# ArbotixProv11.net
KiCad netlist of a schematic drawn in EAGLE
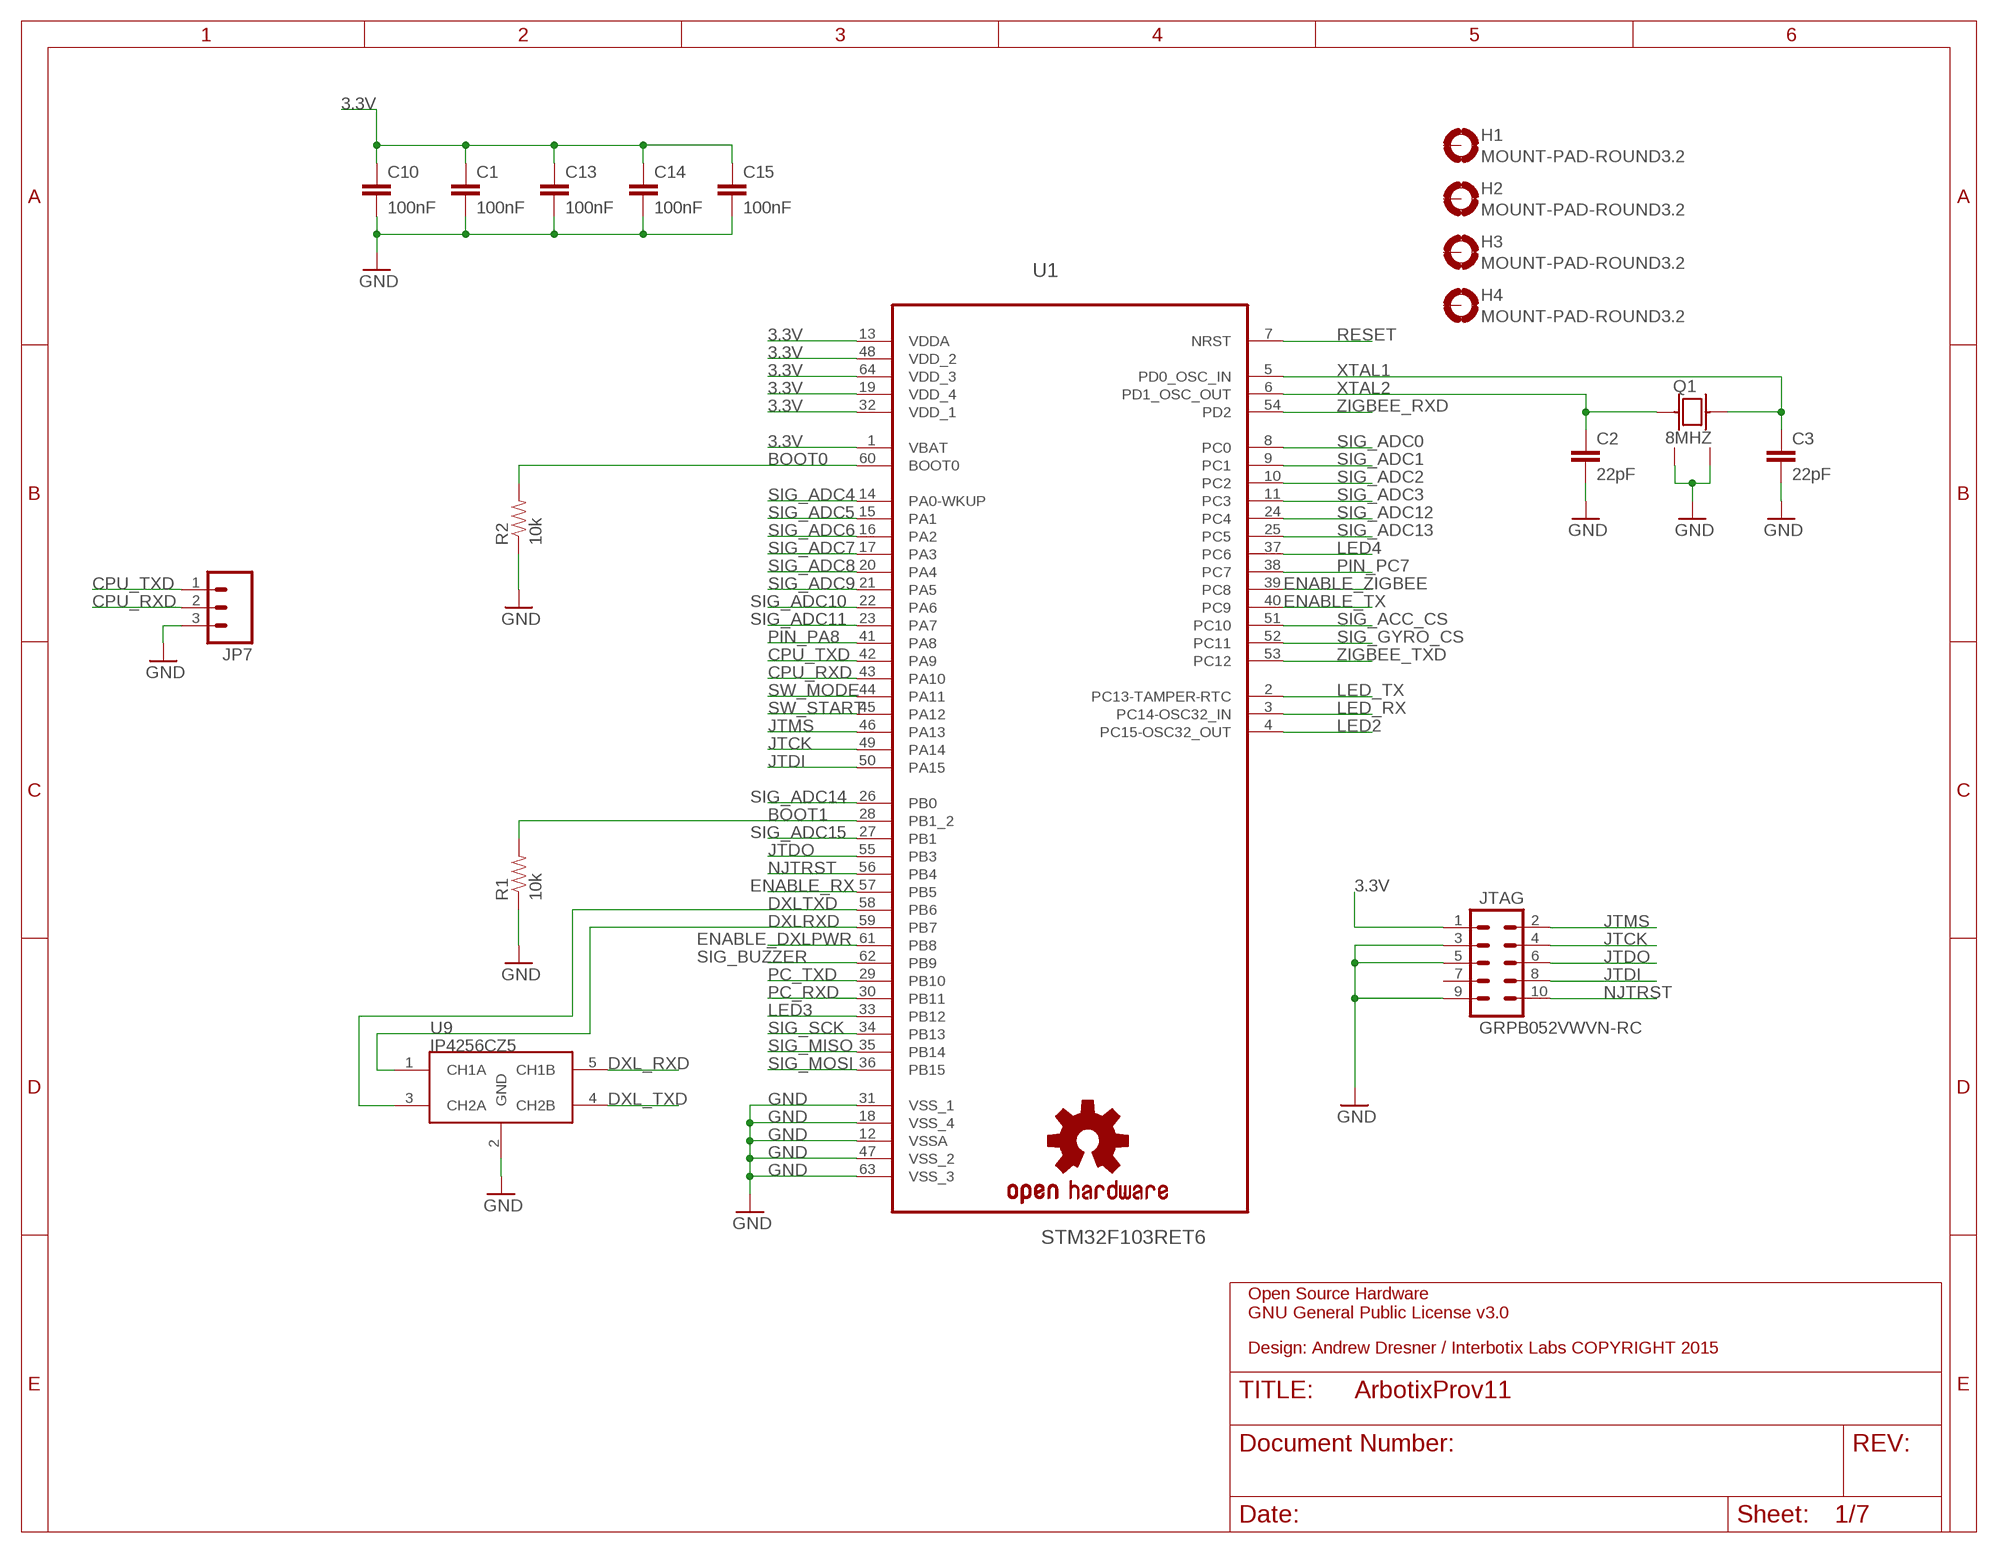
[diagram p0: schematic, sheet 1]
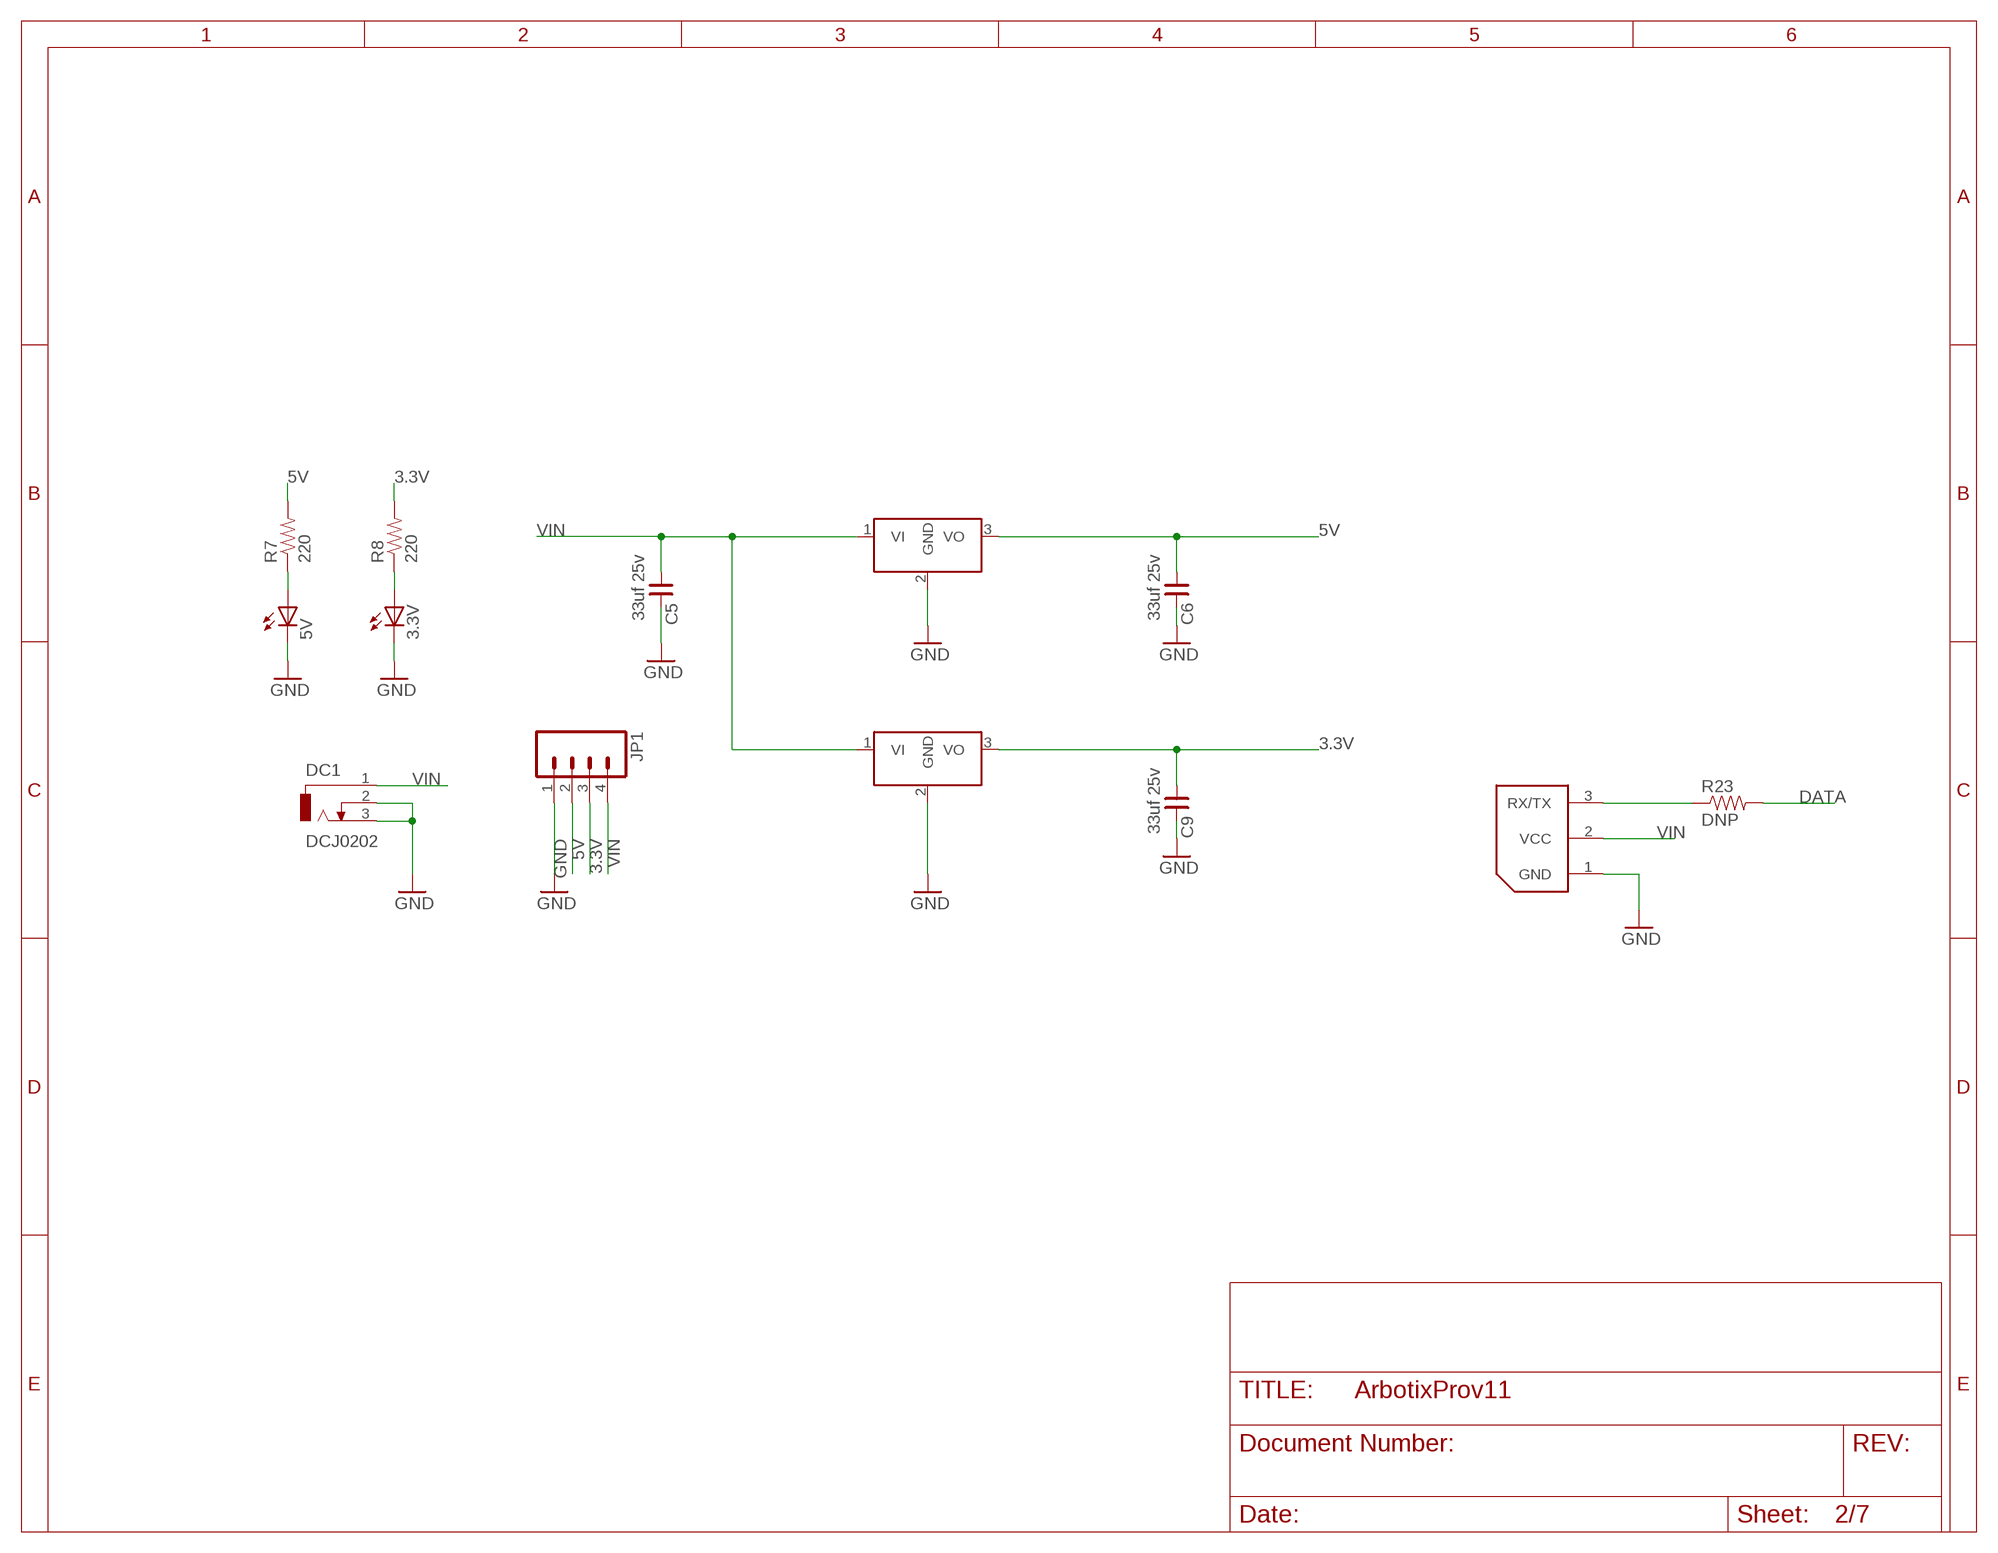
[diagram p1: schematic, sheet 2]
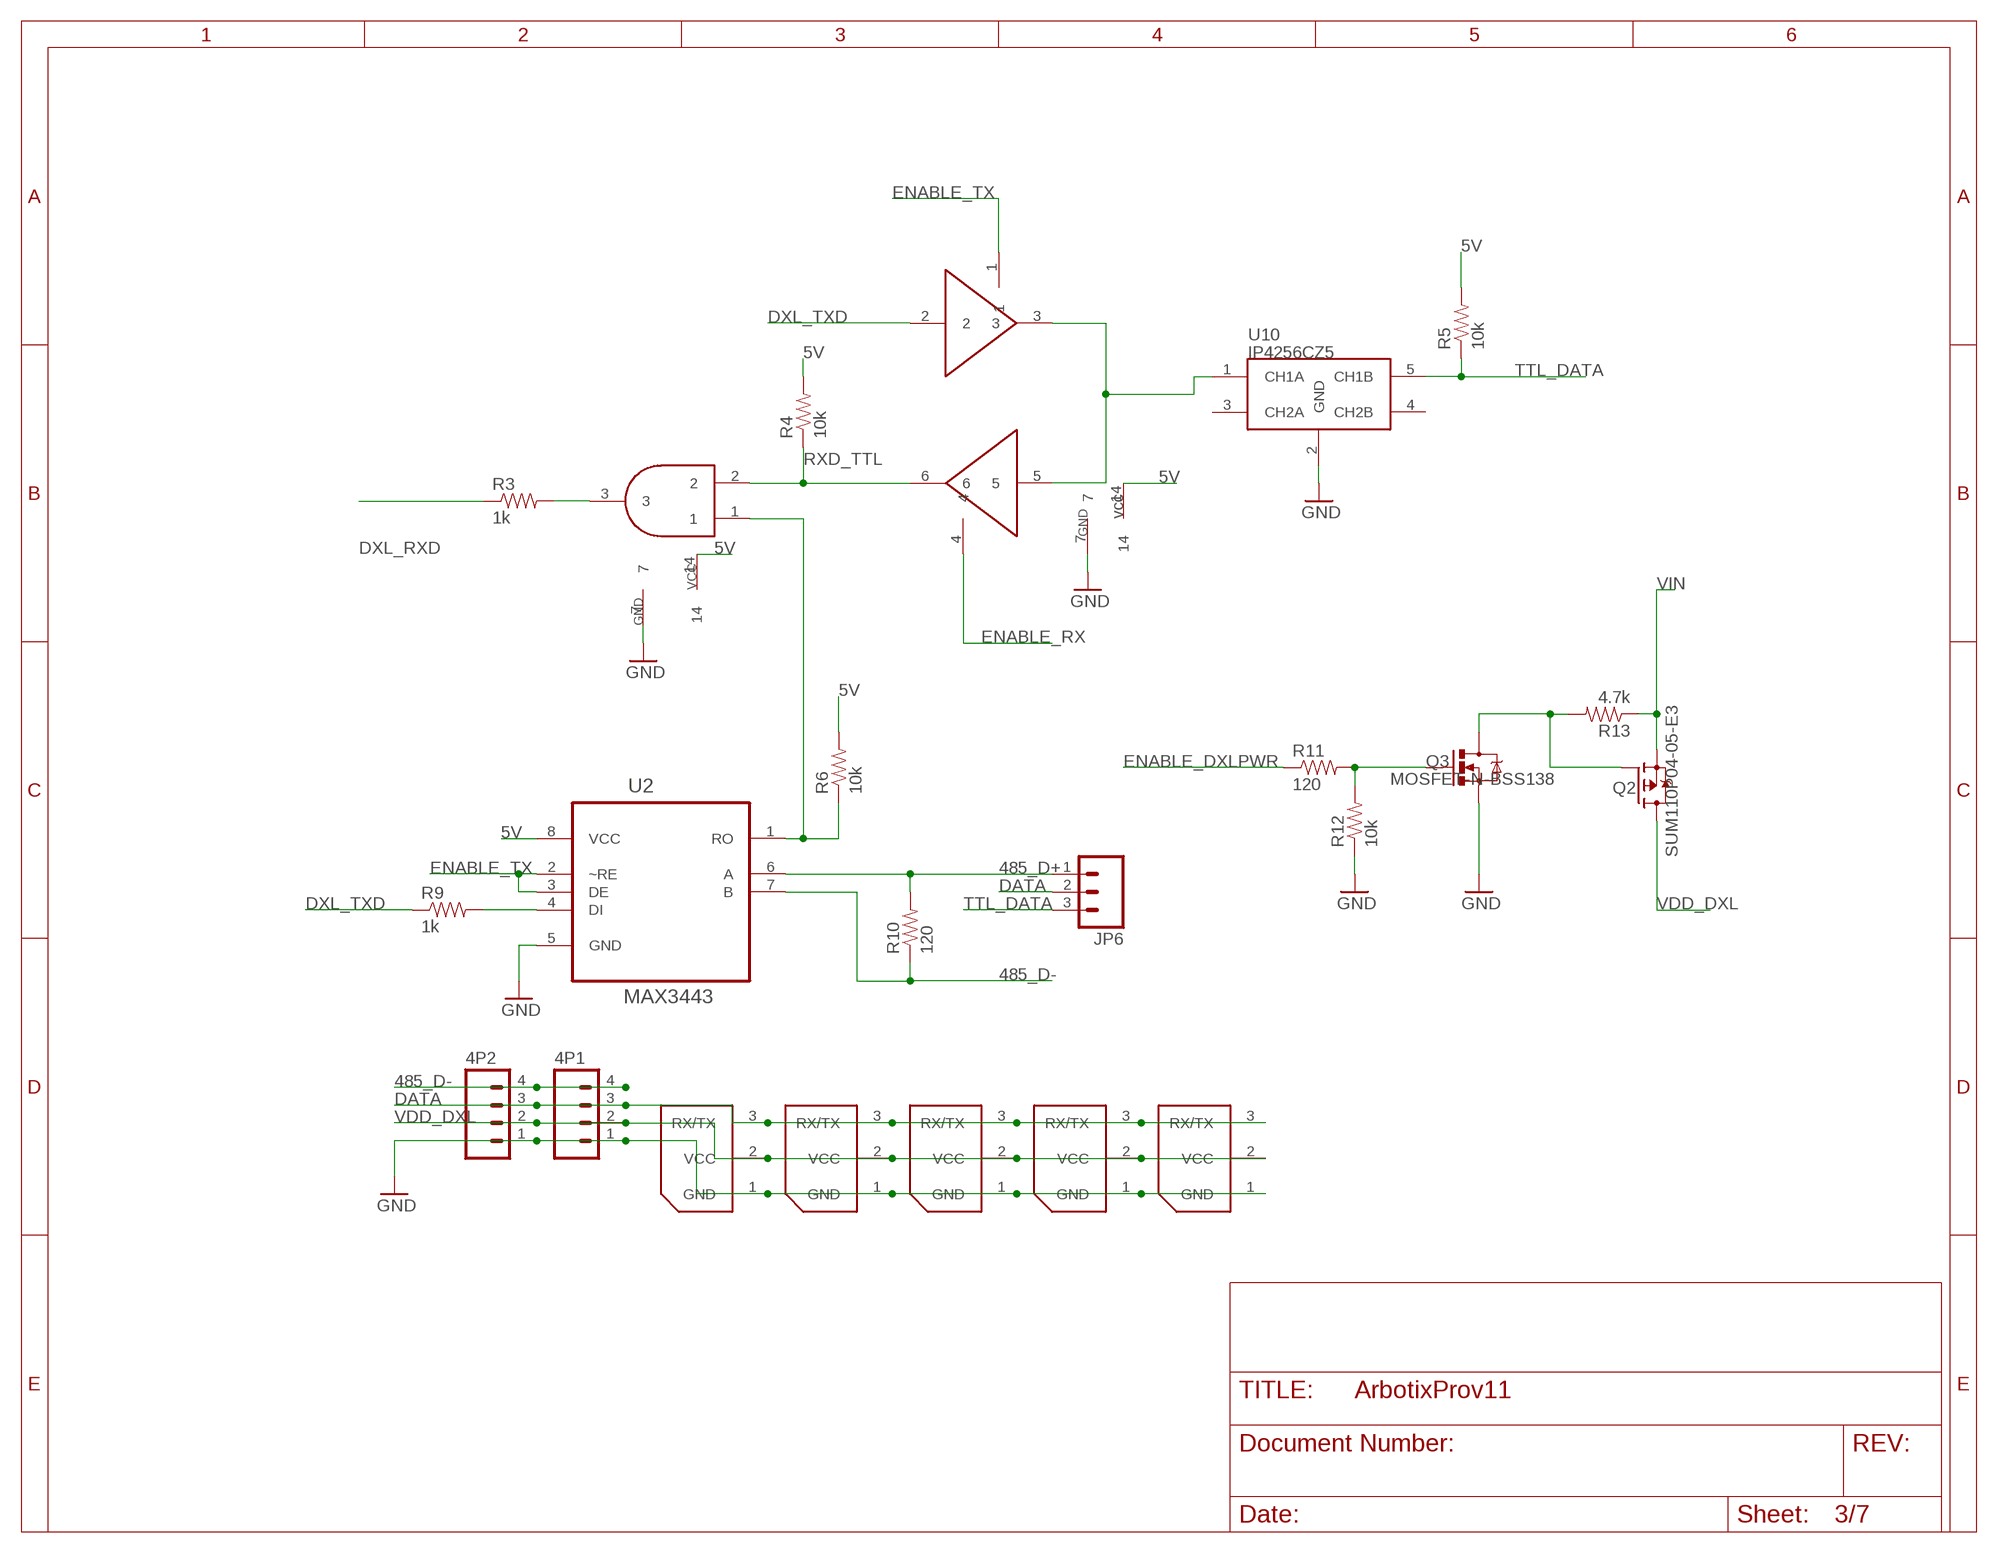
[diagram p2: schematic, sheet 3]
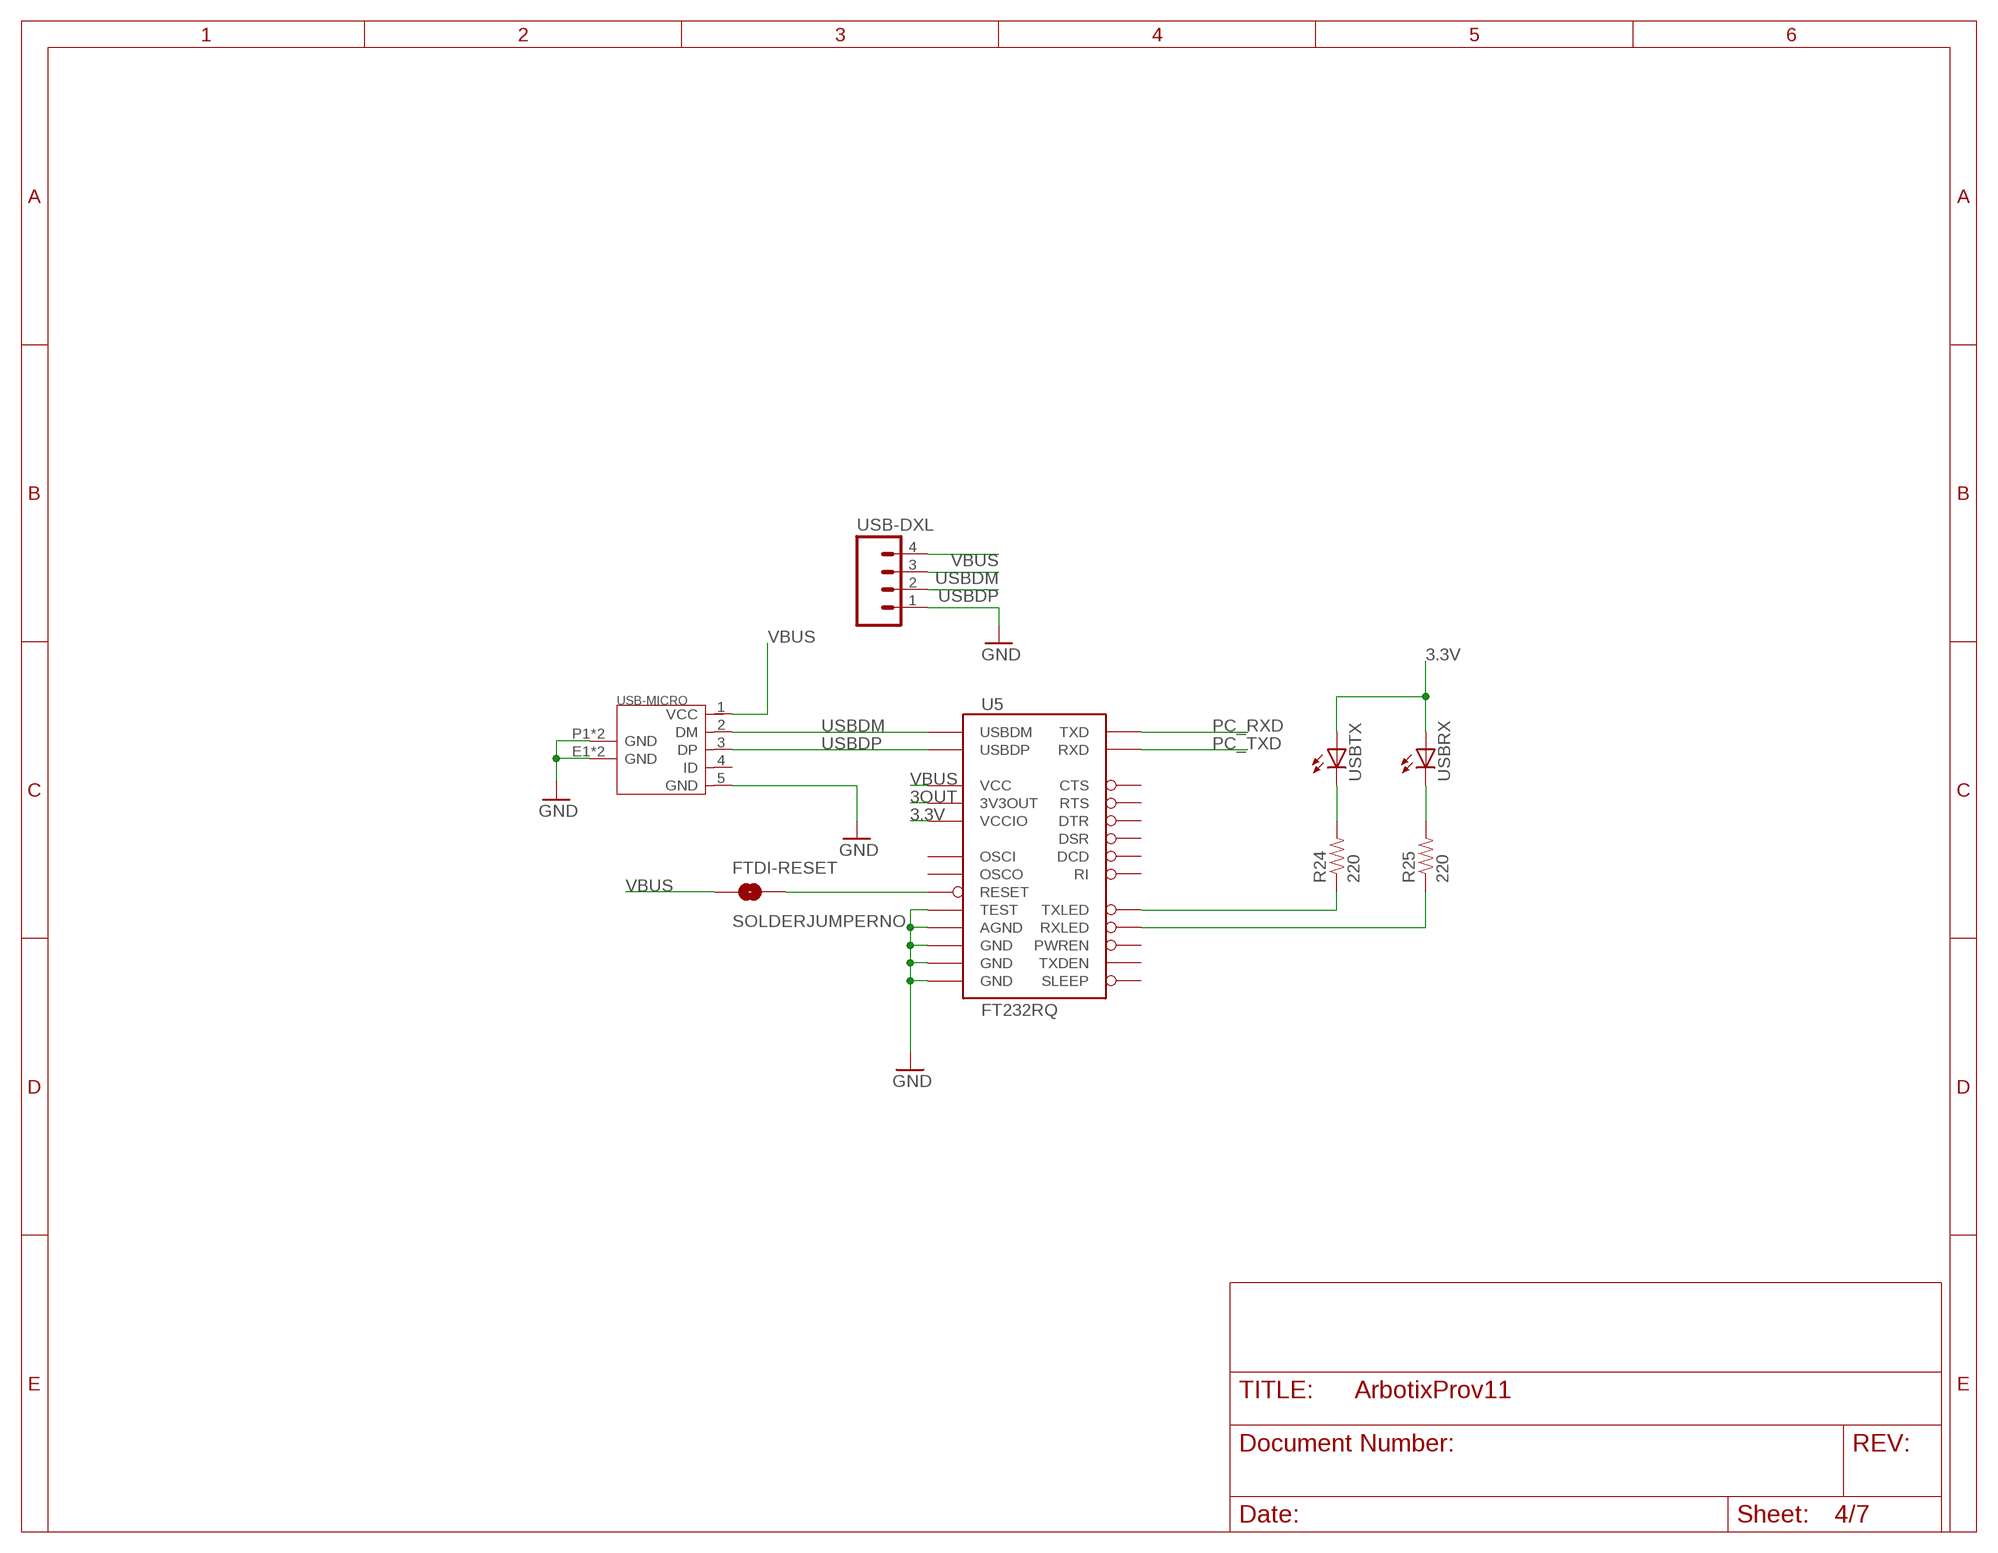
[diagram p3: schematic, sheet 4]
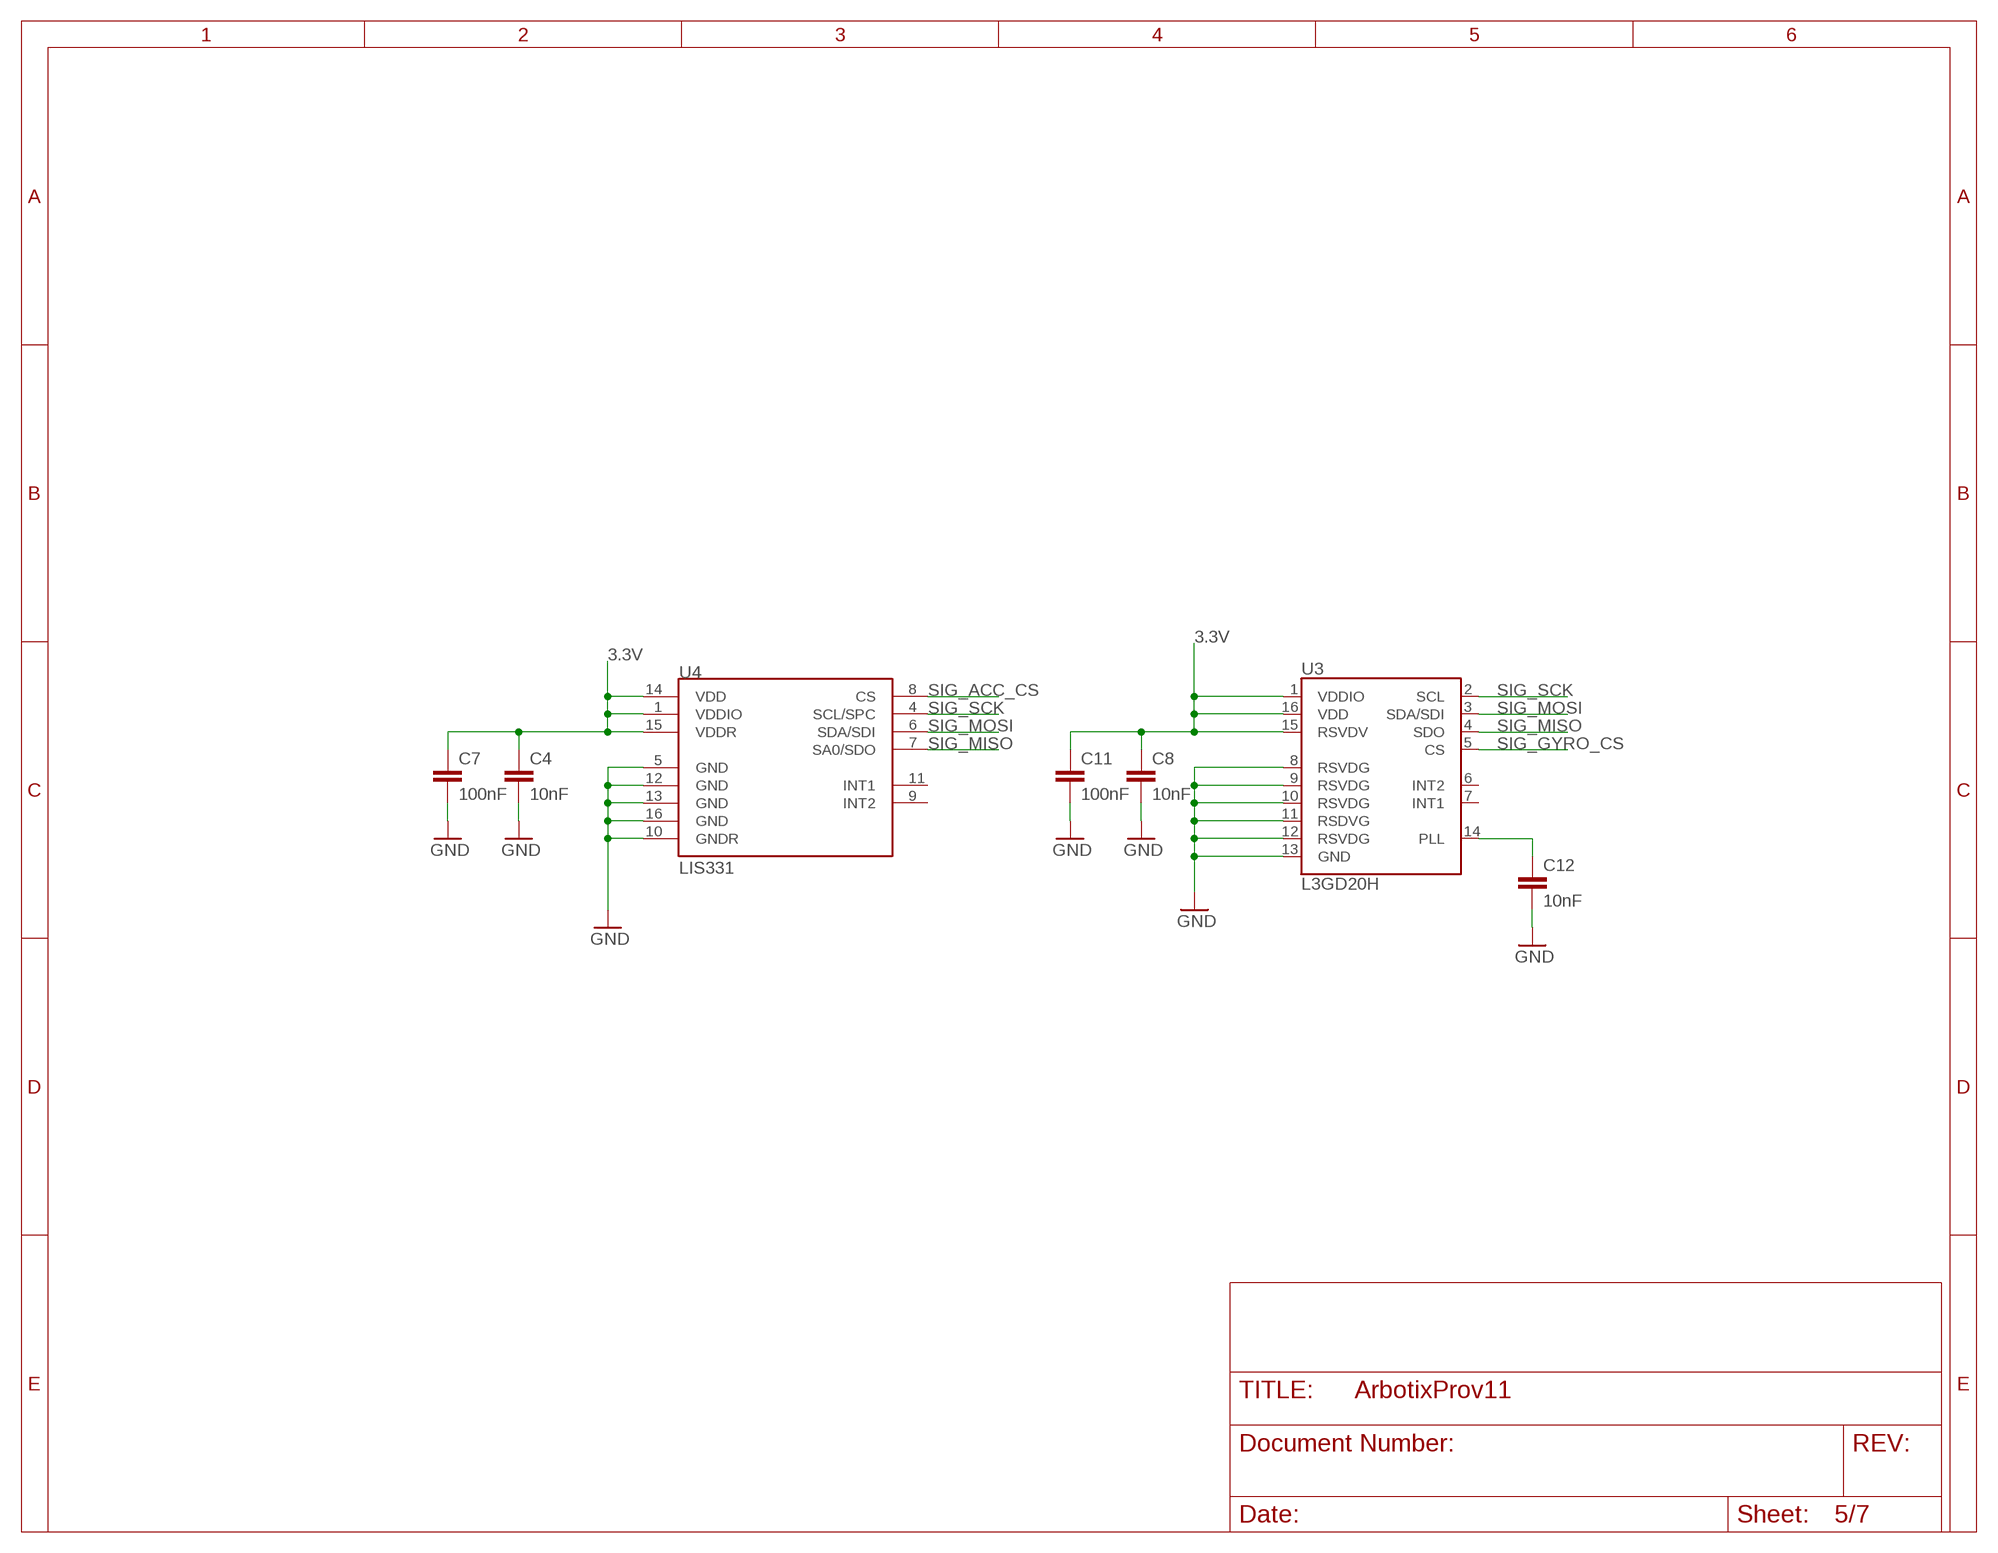
[diagram p4: schematic, sheet 5]
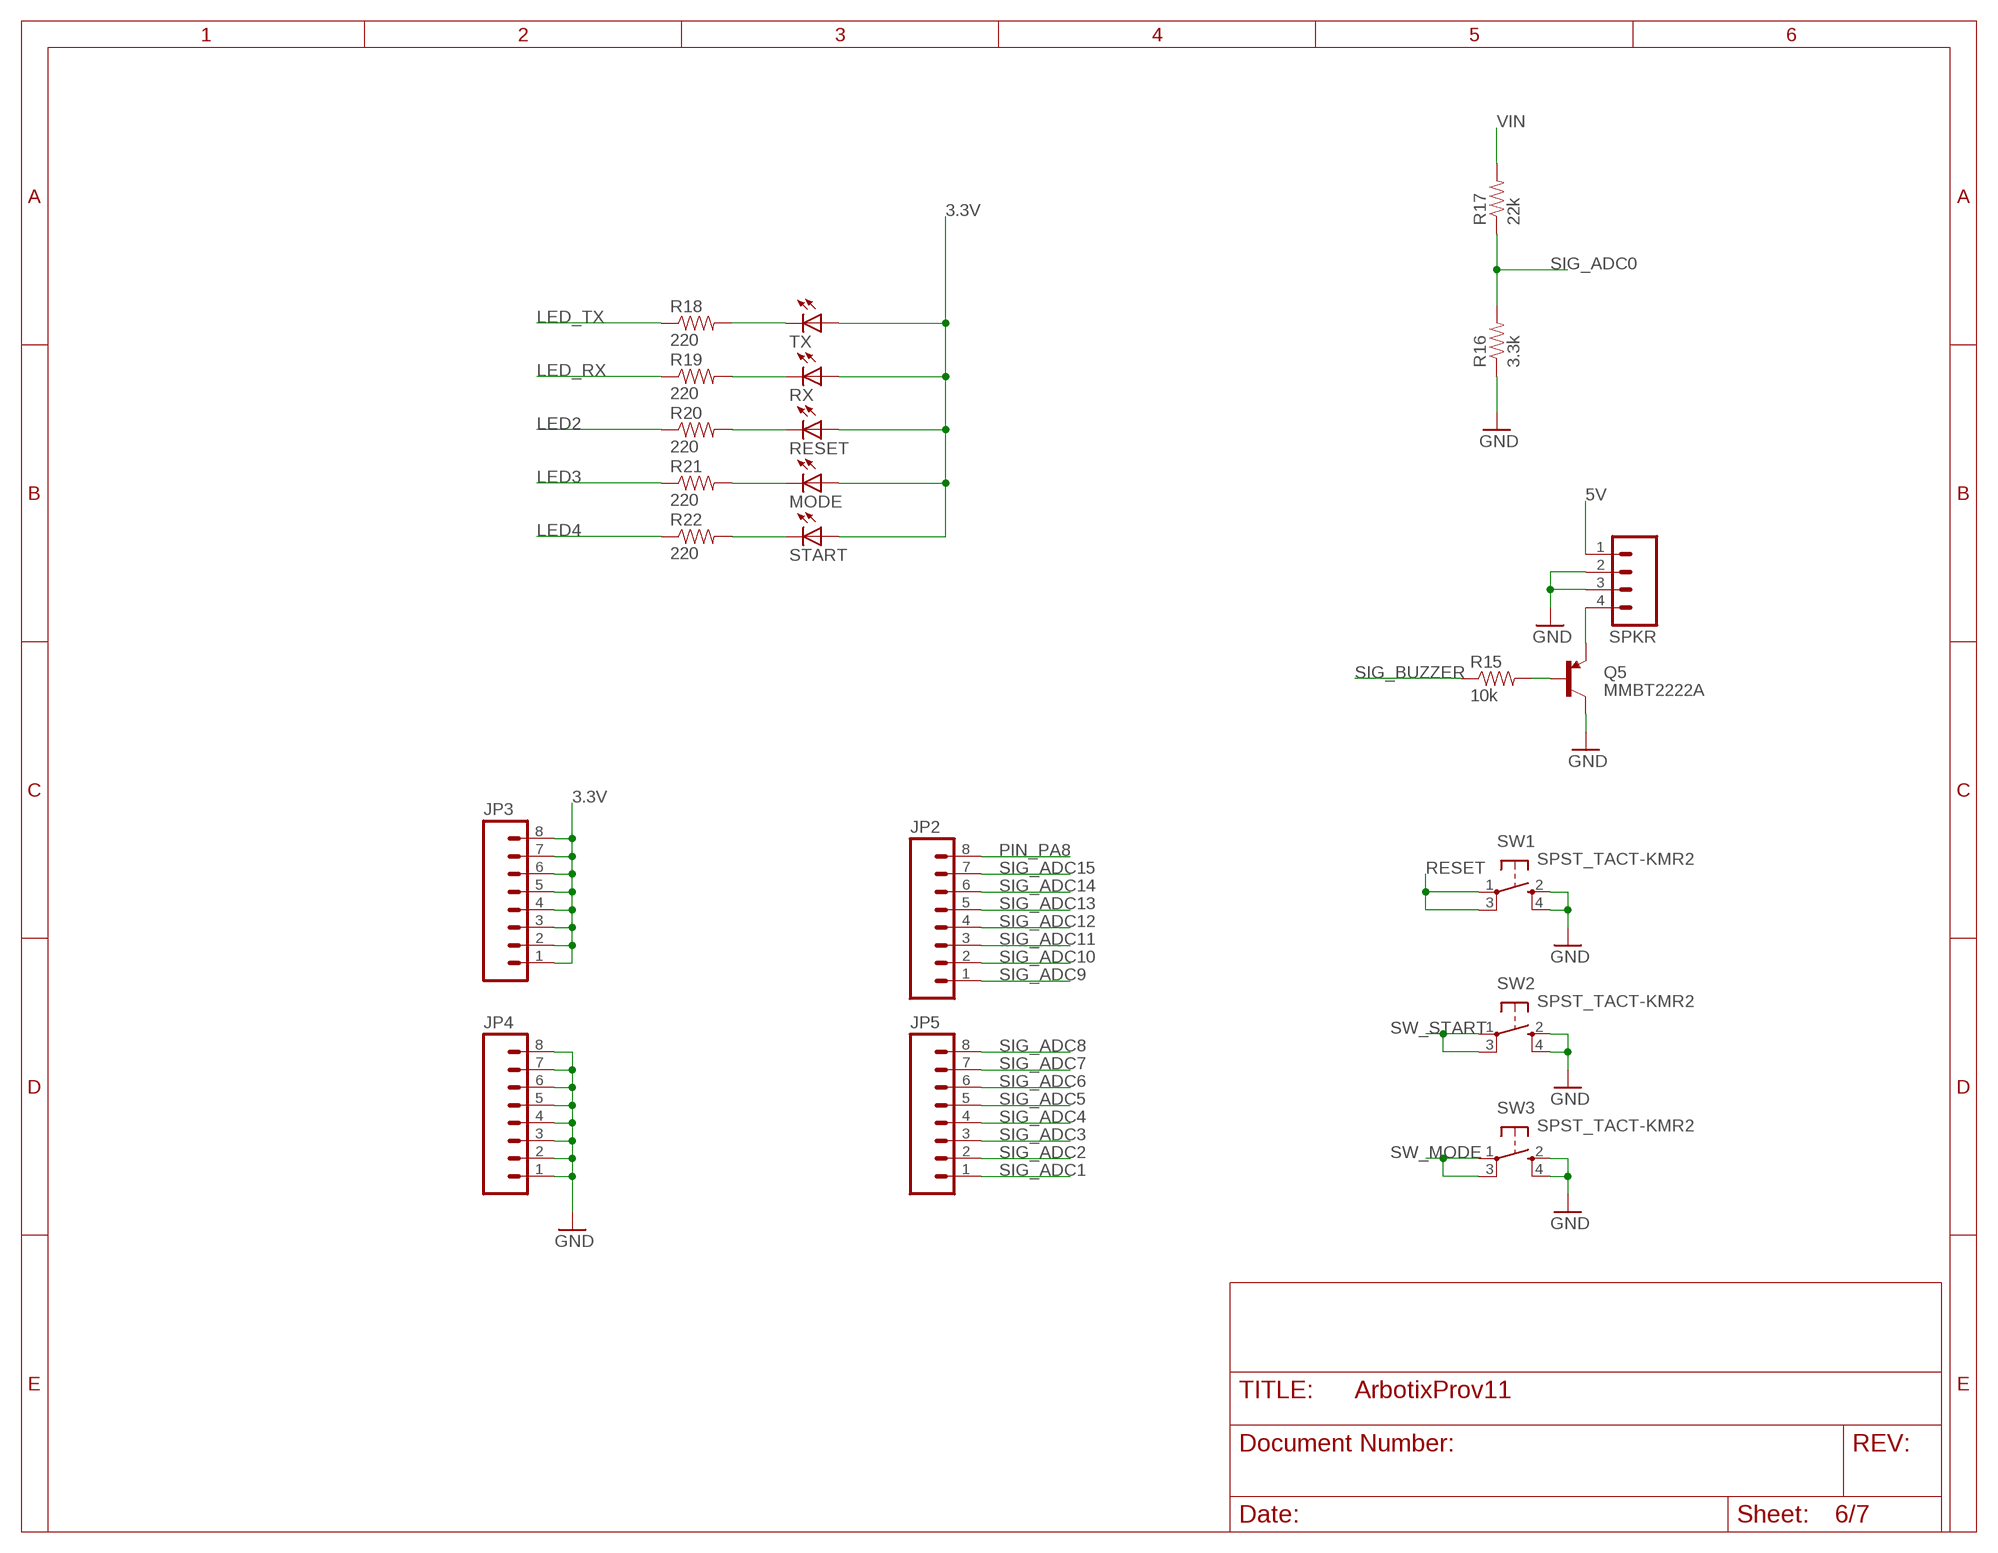
[diagram p5: schematic, sheet 6]
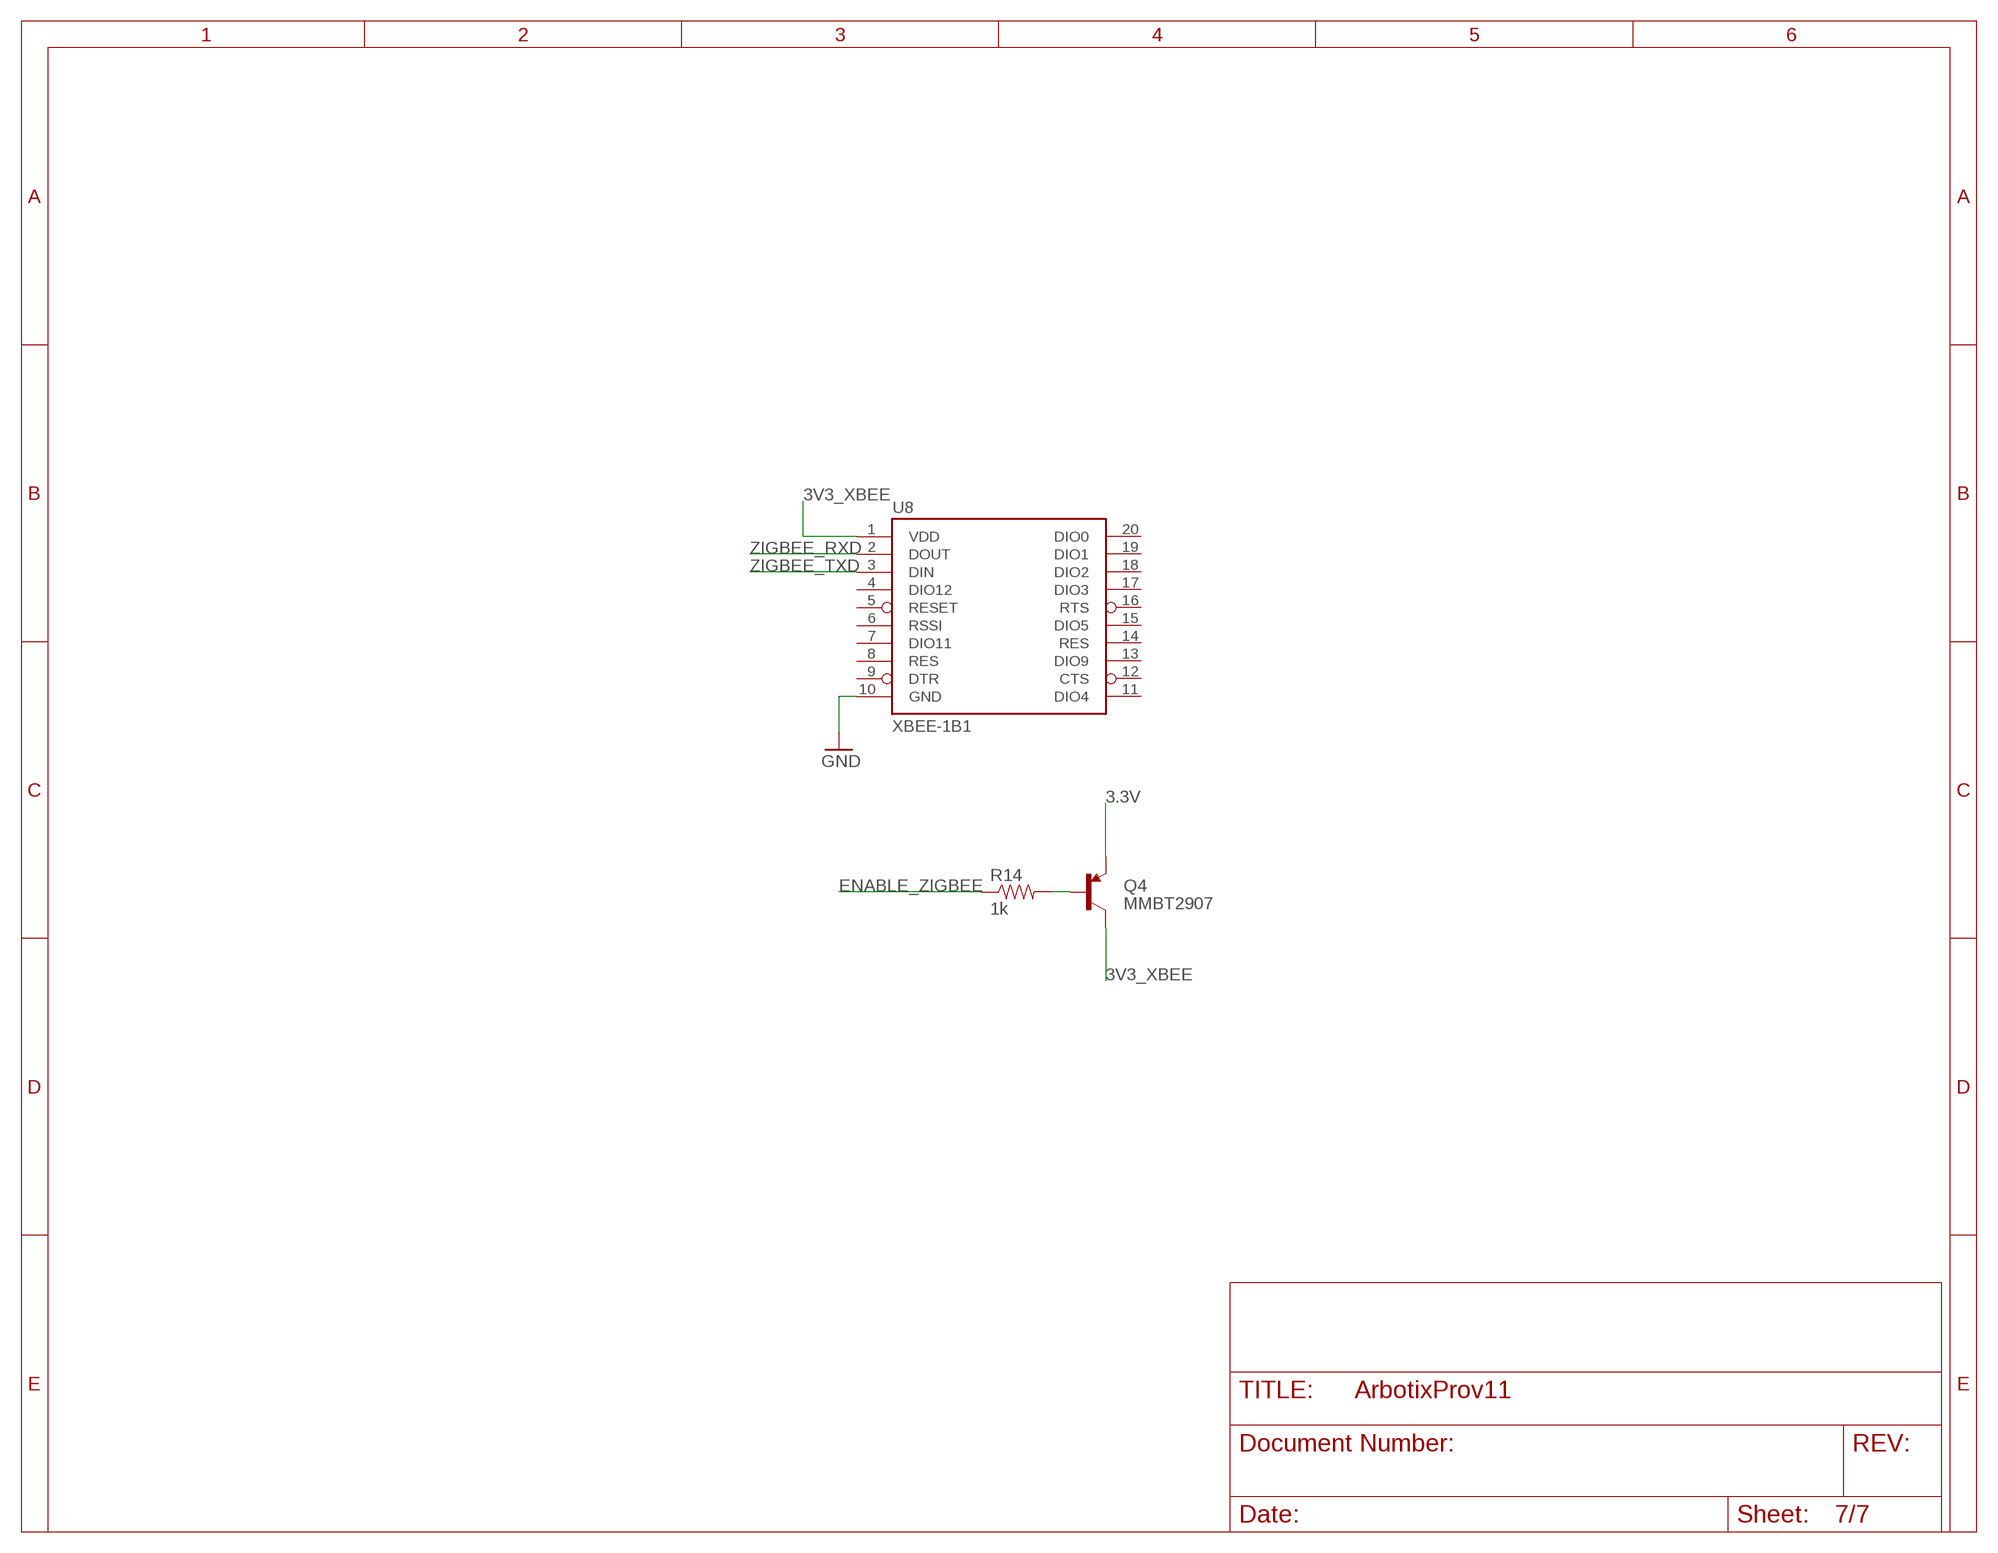
[diagram p6: schematic, sheet 7]

(export (version "E")
  (design (tool "Eeschema 10.0.6"))
  (components
    (comp (ref "FTDI-RESET")
      (value "SOLDERJUMPERNO")
      (footprint "eagle-import:SJ_2S-NO")
      (libsource (lib "eagle-import") (part "SOLDERJUMPERNO"))
    )
    (comp (ref "R24")
      (value "220")
      (footprint "eagle-import:0603-RES")
      (libsource (lib "eagle-import") (part "RESISTOR0603"))
    )
    (comp (ref "R25")
      (value "220")
      (footprint "eagle-import:0603-RES")
      (libsource (lib "eagle-import") (part "RESISTOR0603"))
    )
    (comp (ref "U5")
      (value "FT232RQ")
      (footprint "eagle-import:QFN-32")
      (libsource (lib "eagle-import") (part "FT232RQ"))
    )
    (comp (ref "USB-DXL")
      (value "M04PTH")
      (footprint "eagle-import:1X04")
      (libsource (lib "eagle-import") (part "M04PTH"))
    )
    (comp (ref "USB-MICRO")
      (value "MICRO-USB-5P-340015001")
      (footprint "eagle-import:B-SMD-5P")
      (libsource (lib "eagle-import") (part "MICRO-USB-5P-340015001"))
    )
    (comp (ref "USBRX")
      (value "LEDCHIPLED_0603")
      (footprint "eagle-import:CHIPLED_0603")
      (libsource (lib "eagle-import") (part "LEDCHIPLED_0603"))
    )
    (comp (ref "USBTX")
      (value "LEDCHIPLED_0603")
      (footprint "eagle-import:CHIPLED_0603")
      (libsource (lib "eagle-import") (part "LEDCHIPLED_0603"))
    )
    (comp (ref "Q4")
      (value "MMBT2907")
      (footprint "eagle-import:SOT23")
      (libsource (lib "eagle-import") (part "TRANSISTOR_PNPMMBT4403"))
    )
    (comp (ref "R14")
      (value "1k")
      (footprint "eagle-import:0603-RES")
      (libsource (lib "eagle-import") (part "RESISTOR0603-RES"))
    )
    (comp (ref "U8")
      (value "XBEE-1B1")
      (footprint "eagle-import:XBEE-1")
      (libsource (lib "eagle-import") (part "XBEE-1B1"))
    )
    (comp (ref "3P1")
      (value "WM18887-ND")
      (footprint "eagle-import:BIOLOID")
      (libsource (lib "eagle-import") (part "WM18887-ND"))
    )
    (comp (ref "3P2")
      (value "WM18887-ND")
      (footprint "eagle-import:BIOLOID")
      (libsource (lib "eagle-import") (part "WM18887-ND"))
    )
    (comp (ref "3P3")
      (value "WM18887-ND")
      (footprint "eagle-import:BIOLOID")
      (libsource (lib "eagle-import") (part "WM18887-ND"))
    )
    (comp (ref "3P4")
      (value "WM18887-ND")
      (footprint "eagle-import:BIOLOID")
      (libsource (lib "eagle-import") (part "WM18887-ND"))
    )
    (comp (ref "3P5")
      (value "WM18887-ND")
      (footprint "eagle-import:BIOLOID")
      (libsource (lib "eagle-import") (part "WM18887-ND"))
    )
    (comp (ref "4P1")
      (value "M04PTH")
      (footprint "eagle-import:1X04")
      (libsource (lib "eagle-import") (part "M04PTH"))
    )
    (comp (ref "4P2")
      (value "M04PTH")
      (footprint "eagle-import:1X04")
      (libsource (lib "eagle-import") (part "M04PTH"))
    )
    (comp (ref "JP6")
      (value "M03PTH")
      (footprint "eagle-import:1X03")
      (libsource (lib "eagle-import") (part "M03PTH"))
    )
    (comp (ref "Q2")
      (value "SUM110P04-05-E3")
      (footprint "eagle-import:TO263")
      (libsource (lib "eagle-import") (part "SPB80P06P"))
    )
    (comp (ref "Q3")
      (value "MOSFET-N-BSS138")
      (footprint "eagle-import:SOT23")
      (libsource (lib "eagle-import") (part "MOSFET-NCHANNELBSS138"))
    )
    (comp (ref "R3")
      (value "1k")
      (footprint "eagle-import:0603-RES")
      (libsource (lib "eagle-import") (part "RESISTOR0603-RES"))
    )
    (comp (ref "R4")
      (value "10k")
      (footprint "eagle-import:0603-RES")
      (libsource (lib "eagle-import") (part "RESISTOR0603-RES"))
    )
    (comp (ref "R5")
      (value "10k")
      (footprint "eagle-import:0603-RES")
      (libsource (lib "eagle-import") (part "RESISTOR0603-RES"))
    )
    (comp (ref "R6")
      (value "10k")
      (footprint "eagle-import:0603-RES")
      (libsource (lib "eagle-import") (part "RESISTOR0603-RES"))
    )
    (comp (ref "R9")
      (value "1k")
      (footprint "eagle-import:0603-RES")
      (libsource (lib "eagle-import") (part "RESISTOR0603-RES"))
    )
    (comp (ref "R10")
      (value "120")
      (footprint "eagle-import:0603-RES")
      (libsource (lib "eagle-import") (part "RESISTOR0603-RES"))
    )
    (comp (ref "R11")
      (value "120")
      (footprint "eagle-import:0603-RES")
      (libsource (lib "eagle-import") (part "RESISTOR0603-RES"))
    )
    (comp (ref "R12")
      (value "10k")
      (footprint "eagle-import:0603-RES")
      (libsource (lib "eagle-import") (part "RESISTOR0603-RES"))
    )
    (comp (ref "R13")
      (value "4.7k")
      (footprint "eagle-import:0603-RES")
      (libsource (lib "eagle-import") (part "RESISTOR0603-RES"))
    )
    (comp (ref "U2")
      (value "MAX3443")
      (footprint "eagle-import:SOIC127P600X175-8N")
      (fields (field (name "MPN") "MAX3443EESA+"))
      (libsource (lib "eagle-import") (part "MAX3443EESA+"))
    )
    (comp (ref "U6")
      (value "74HC08D,653")
      (footprint "eagle-import:14-SOIC")
      (libsource (lib "eagle-import") (part "74HCT08D,653"))
    )
    (comp (ref "U7")
      (value "74HC126D,653")
      (footprint "eagle-import:14-SOIC")
      (libsource (lib "eagle-import") (part "74HC126D,653"))
    )
    (comp (ref "U10")
      (value "IP4256CZ5")
      (footprint "eagle-import:SOT665")
      (libsource (lib "eagle-import") (part "IP4256CZ5-W,115"))
    )
    (comp (ref "C1")
      (value "100nF")
      (footprint "eagle-import:0603-CAP")
      (libsource (lib "eagle-import") (part "CAP0603-CAP"))
    )
    (comp (ref "C2")
      (value "22pF")
      (footprint "eagle-import:0603-CAP")
      (libsource (lib "eagle-import") (part "22PF-50V-5%(0603)"))
    )
    (comp (ref "C3")
      (value "22pF")
      (footprint "eagle-import:0603-CAP")
      (libsource (lib "eagle-import") (part "22PF-50V-5%(0603)"))
    )
    (comp (ref "C10")
      (value "100nF")
      (footprint "eagle-import:0603-CAP")
      (libsource (lib "eagle-import") (part "CAP0603-CAP"))
    )
    (comp (ref "C13")
      (value "100nF")
      (footprint "eagle-import:0603-CAP")
      (libsource (lib "eagle-import") (part "CAP0603-CAP"))
    )
    (comp (ref "C14")
      (value "100nF")
      (footprint "eagle-import:0603-CAP")
      (libsource (lib "eagle-import") (part "CAP0603-CAP"))
    )
    (comp (ref "C15")
      (value "100nF")
      (footprint "eagle-import:0603-CAP")
      (libsource (lib "eagle-import") (part "CAP0603-CAP"))
    )
    (comp (ref "H1")
      (value "MOUNT-PAD-ROUND3.2")
      (footprint "eagle-import:3,2-PAD")
      (libsource (lib "eagle-import") (part "MOUNT-PAD-ROUND3.2"))
    )
    (comp (ref "H2")
      (value "MOUNT-PAD-ROUND3.2")
      (footprint "eagle-import:3,2-PAD")
      (libsource (lib "eagle-import") (part "MOUNT-PAD-ROUND3.2"))
    )
    (comp (ref "H3")
      (value "MOUNT-PAD-ROUND3.2")
      (footprint "eagle-import:3,2-PAD")
      (libsource (lib "eagle-import") (part "MOUNT-PAD-ROUND3.2"))
    )
    (comp (ref "H4")
      (value "MOUNT-PAD-ROUND3.2")
      (footprint "eagle-import:3,2-PAD")
      (libsource (lib "eagle-import") (part "MOUNT-PAD-ROUND3.2"))
    )
    (comp (ref "JP7")
      (value "M03PTH")
      (footprint "eagle-import:1X03")
      (libsource (lib "eagle-import") (part "M03PTH"))
    )
    (comp (ref "JTAG")
      (value "GRPB052VWVN-RC")
      (footprint "eagle-import:2X5_PTH_SILK_.05")
      (libsource (lib "eagle-import") (part "M05X20.05_IN_PTH_SILK"))
    )
    (comp (ref "LOGO1")
      (value "OSHW-LOGOM")
      (footprint "eagle-import:OSHW-LOGO-M")
      (libsource (lib "eagle-import") (part "OSHW-LOGOM"))
    )
    (comp (ref "Q1")
      (value "8MHZ")
      (footprint "eagle-import:4LCC")
      (libsource (lib "eagle-import") (part "AMB3B-25.000MHZ-B2-T8MHZ8MHZ"))
    )
    (comp (ref "R1")
      (value "10k")
      (footprint "eagle-import:0603-RES")
      (libsource (lib "eagle-import") (part "RESISTOR0603-RES"))
    )
    (comp (ref "R2")
      (value "10k")
      (footprint "eagle-import:0603-RES")
      (libsource (lib "eagle-import") (part "RESISTOR0603-RES"))
    )
    (comp (ref "U1")
      (value "STM32F103RET6")
      (footprint "eagle-import:QFP50P1200X1200X160-64N")
      (libsource (lib "eagle-import") (part "STM32F103RET6"))
    )
    (comp (ref "U9")
      (value "IP4256CZ5")
      (footprint "eagle-import:SOT665")
      (libsource (lib "eagle-import") (part "IP4256CZ5-W,115"))
    )
    (comp (ref "3.3V")
      (value "LEDCHIPLED_0603")
      (footprint "eagle-import:CHIPLED_0603")
      (libsource (lib "eagle-import") (part "LEDCHIPLED_0603"))
    )
    (comp (ref "3V3REG")
      (value "DCDC_OKI-78SR-3.3")
      (footprint "eagle-import:OKI-78SRH")
      (libsource (lib "eagle-import") (part "DCDC_OKI-78SR"))
    )
    (comp (ref "5V")
      (value "LEDCHIPLED_0603")
      (footprint "eagle-import:CHIPLED_0603")
      (libsource (lib "eagle-import") (part "LEDCHIPLED_0603"))
    )
    (comp (ref "5VREG")
      (value "DCDC_OKI-78SR-5")
      (footprint "eagle-import:OKI-78SRH")
      (libsource (lib "eagle-import") (part "DCDC_OKI-78SR"))
    )
    (comp (ref "C5")
      (value "33uf 25v")
      (footprint "eagle-import:SV-C")
      (libsource (lib "eagle-import") (part "CBP-SV-C"))
    )
    (comp (ref "C6")
      (value "33uf 25v")
      (footprint "eagle-import:SV-C")
      (libsource (lib "eagle-import") (part "CBP-SV-C"))
    )
    (comp (ref "C9")
      (value "33uf 25v")
      (footprint "eagle-import:SV-C")
      (libsource (lib "eagle-import") (part "CBP-SV-C"))
    )
    (comp (ref "CPU-POWER")
      (value "WM18887-ND")
      (footprint "eagle-import:BIOLOID")
      (libsource (lib "eagle-import") (part "WM18887-ND"))
    )
    (comp (ref "DC1")
      (value "DCJ0202")
      (footprint "eagle-import:DCJ0202")
      (libsource (lib "eagle-import") (part "DCJ0202"))
    )
    (comp (ref "JP1")
      (value "M04PTH")
      (footprint "eagle-import:1X04")
      (libsource (lib "eagle-import") (part "M04PTH"))
    )
    (comp (ref "R7")
      (value "220")
      (footprint "eagle-import:0603-RES")
      (libsource (lib "eagle-import") (part "RESISTOR0603"))
    )
    (comp (ref "R8")
      (value "220")
      (footprint "eagle-import:0603-RES")
      (libsource (lib "eagle-import") (part "RESISTOR0603"))
    )
    (comp (ref "R23")
      (value "DNP")
      (footprint "eagle-import:0603-RES")
      (libsource (lib "eagle-import") (part "RESISTOR0603"))
    )
    (comp (ref "JP2")
      (value "M08SILK_FEMALE_PTH")
      (footprint "eagle-import:1X08")
      (libsource (lib "eagle-import") (part "M08SILK_FEMALE_PTH"))
    )
    (comp (ref "JP3")
      (value "M08SILK_FEMALE_PTH")
      (footprint "eagle-import:1X08")
      (libsource (lib "eagle-import") (part "M08SILK_FEMALE_PTH"))
    )
    (comp (ref "JP4")
      (value "M08SILK_FEMALE_PTH")
      (footprint "eagle-import:1X08")
      (libsource (lib "eagle-import") (part "M08SILK_FEMALE_PTH"))
    )
    (comp (ref "JP5")
      (value "M08SILK_FEMALE_PTH")
      (footprint "eagle-import:1X08")
      (libsource (lib "eagle-import") (part "M08SILK_FEMALE_PTH"))
    )
    (comp (ref "MODE")
      (value "LEDCHIP-LED0603")
      (footprint "eagle-import:CHIP-LED0603")
      (libsource (lib "eagle-import") (part "LEDCHIP-LED0603"))
    )
    (comp (ref "Q5")
      (value "MMBT2222A")
      (footprint "eagle-import:SOT23")
      (libsource (lib "eagle-import") (part "TRANSISTOR_PNPMMBT4403"))
    )
    (comp (ref "R15")
      (value "10k")
      (footprint "eagle-import:0603-RES")
      (libsource (lib "eagle-import") (part "RESISTOR0603-RES"))
    )
    (comp (ref "R16")
      (value "3.3k")
      (footprint "eagle-import:0603-RES")
      (libsource (lib "eagle-import") (part "RESISTOR0603-RES"))
    )
    (comp (ref "R17")
      (value "22k")
      (footprint "eagle-import:0603-RES")
      (libsource (lib "eagle-import") (part "RESISTOR0603-RES"))
    )
    (comp (ref "R18")
      (value "220")
      (footprint "eagle-import:0603-RES")
      (libsource (lib "eagle-import") (part "RESISTOR0603-RES"))
    )
    (comp (ref "R19")
      (value "220")
      (footprint "eagle-import:0603-RES")
      (libsource (lib "eagle-import") (part "RESISTOR0603-RES"))
    )
    (comp (ref "R20")
      (value "220")
      (footprint "eagle-import:0603-RES")
      (libsource (lib "eagle-import") (part "RESISTOR0603-RES"))
    )
    (comp (ref "R21")
      (value "220")
      (footprint "eagle-import:0603-RES")
      (libsource (lib "eagle-import") (part "RESISTOR0603-RES"))
    )
    (comp (ref "R22")
      (value "220")
      (footprint "eagle-import:0603-RES")
      (libsource (lib "eagle-import") (part "RESISTOR0603-RES"))
    )
    (comp (ref "RESET")
      (value "LEDCHIP-LED0603")
      (footprint "eagle-import:CHIP-LED0603")
      (libsource (lib "eagle-import") (part "LEDCHIP-LED0603"))
    )
    (comp (ref "RX")
      (value "LEDCHIP-LED0603")
      (footprint "eagle-import:CHIP-LED0603")
      (libsource (lib "eagle-import") (part "LEDCHIP-LED0603"))
    )
    (comp (ref "SPKR")
      (value "M04PTH")
      (footprint "eagle-import:1X04")
      (libsource (lib "eagle-import") (part "M04PTH"))
    )
    (comp (ref "START")
      (value "LEDCHIP-LED0603")
      (footprint "eagle-import:CHIP-LED0603")
      (libsource (lib "eagle-import") (part "LEDCHIP-LED0603"))
    )
    (comp (ref "SW1")
      (value "SPST_TACT-KMR2")
      (footprint "eagle-import:KMR2")
      (libsource (lib "eagle-import") (part "SPST_TACT-KMR2"))
    )
    (comp (ref "SW2")
      (value "SPST_TACT-KMR2")
      (footprint "eagle-import:KMR2")
      (libsource (lib "eagle-import") (part "SPST_TACT-KMR2"))
    )
    (comp (ref "SW3")
      (value "SPST_TACT-KMR2")
      (footprint "eagle-import:KMR2")
      (libsource (lib "eagle-import") (part "SPST_TACT-KMR2"))
    )
    (comp (ref "TX")
      (value "LEDCHIP-LED0603")
      (footprint "eagle-import:CHIP-LED0603")
      (libsource (lib "eagle-import") (part "LEDCHIP-LED0603"))
    )
    (comp (ref "C4")
      (value "10nF")
      (footprint "eagle-import:0603-CAP")
      (libsource (lib "eagle-import") (part "CAP0603-CAP"))
    )
    (comp (ref "C7")
      (value "100nF")
      (footprint "eagle-import:0603-CAP")
      (libsource (lib "eagle-import") (part "CAP0603-CAP"))
    )
    (comp (ref "C8")
      (value "10nF")
      (footprint "eagle-import:0603-CAP")
      (libsource (lib "eagle-import") (part "CAP0603-CAP"))
    )
    (comp (ref "C11")
      (value "100nF")
      (footprint "eagle-import:0603-CAP")
      (libsource (lib "eagle-import") (part "CAP0603-CAP"))
    )
    (comp (ref "C12")
      (value "10nF")
      (footprint "eagle-import:0603-CAP")
      (libsource (lib "eagle-import") (part "CAP0603-CAP"))
    )
    (comp (ref "U3")
      (value "L3GD20H")
      (footprint "eagle-import:LGA16-3MM")
      (libsource (lib "eagle-import") (part "L3GD20H"))
    )
    (comp (ref "U4")
      (value "LIS331")
      (footprint "eagle-import:LGA16-3MM")
      (libsource (lib "eagle-import") (part "LIS331"))
    )
  )
  (nets
    (net (code "1") (name "3.3V") (class "Default")
      (node (ref "3V3REG") (pin "3") (pinfunction "VO_3") (pintype "bidirectional"))
      (node (ref "C1") (pin "1") (pinfunction "1_1") (pintype "passive"))
      (node (ref "C10") (pin "1") (pinfunction "1_1") (pintype "passive"))
      (node (ref "C11") (pin "1") (pinfunction "1_1") (pintype "passive"))
      (node (ref "C13") (pin "1") (pinfunction "1_1") (pintype "passive"))
      (node (ref "C14") (pin "1") (pinfunction "1_1") (pintype "passive"))
      (node (ref "C15") (pin "1") (pinfunction "1_1") (pintype "passive"))
      (node (ref "C4") (pin "1") (pinfunction "1_1") (pintype "passive"))
      (node (ref "C7") (pin "1") (pinfunction "1_1") (pintype "passive"))
      (node (ref "C8") (pin "1") (pinfunction "1_1") (pintype "passive"))
      (node (ref "C9") (pin "+") (pinfunction "1_+") (pintype "passive"))
      (node (ref "JP1") (pin "3") (pinfunction "3_3") (pintype "passive"))
      (node (ref "JP3") (pin "1") (pinfunction "1_1") (pintype "passive"))
      (node (ref "JP3") (pin "2") (pinfunction "2_2") (pintype "passive"))
      (node (ref "JP3") (pin "3") (pinfunction "3_3") (pintype "passive"))
      (node (ref "JP3") (pin "4") (pinfunction "4_4") (pintype "passive"))
      (node (ref "JP3") (pin "5") (pinfunction "5_5") (pintype "passive"))
      (node (ref "JP3") (pin "6") (pinfunction "6_6") (pintype "passive"))
      (node (ref "JP3") (pin "7") (pinfunction "7_7") (pintype "passive"))
      (node (ref "JP3") (pin "8") (pinfunction "8_8") (pintype "passive"))
      (node (ref "JTAG") (pin "1") (pinfunction "1_1") (pintype "passive"))
      (node (ref "MODE") (pin "A") (pinfunction "A_A") (pintype "passive"))
      (node (ref "Q4") (pin "2") (pinfunction "E_2") (pintype "passive"))
      (node (ref "R8") (pin "2") (pinfunction "2_2") (pintype "passive"))
      (node (ref "RESET") (pin "A") (pinfunction "A_A") (pintype "passive"))
      (node (ref "RX") (pin "A") (pinfunction "A_A") (pintype "passive"))
      (node (ref "START") (pin "A") (pinfunction "A_A") (pintype "passive"))
      (node (ref "TX") (pin "A") (pinfunction "A_A") (pintype "passive"))
      (node (ref "U1") (pin "1") (pinfunction "VBAT_1") (pintype "input"))
      (node (ref "U1") (pin "13") (pinfunction "VDDA_13") (pintype "power_in"))
      (node (ref "U1") (pin "19") (pinfunction "VDD_4_19") (pintype "power_in"))
      (node (ref "U1") (pin "32") (pinfunction "VDD_1_32") (pintype "power_in"))
      (node (ref "U1") (pin "48") (pinfunction "VDD_2_48") (pintype "power_in"))
      (node (ref "U1") (pin "64") (pinfunction "VDD_3_64") (pintype "power_in"))
      (node (ref "U3") (pin "1") (pinfunction "VDDIO_1") (pintype "bidirectional"))
      (node (ref "U3") (pin "15") (pinfunction "RSVDV_15") (pintype "bidirectional"))
      (node (ref "U3") (pin "16") (pinfunction "VDD_16") (pintype "bidirectional"))
      (node (ref "U4") (pin "1") (pinfunction "VDDIO_1") (pintype "bidirectional"))
      (node (ref "U4") (pin "14") (pinfunction "VDD_14") (pintype "bidirectional"))
      (node (ref "U4") (pin "15") (pinfunction "VDDR_15") (pintype "bidirectional"))
      (node (ref "U5") (pin "1") (pinfunction "VCCIO_1") (pintype "power_in"))
      (node (ref "USBRX") (pin "A") (pinfunction "A_A") (pintype "passive"))
      (node (ref "USBTX") (pin "A") (pinfunction "A_A") (pintype "passive"))
    )
    (net (code "2") (name "3OUT") (class "Default")
      (node (ref "U5") (pin "16") (pinfunction "3V3OUT_16") (pintype "output"))
    )
    (net (code "3") (name "3V3_XBEE") (class "Default")
      (node (ref "Q4") (pin "3") (pinfunction "C_3") (pintype "passive"))
      (node (ref "U8") (pin "1") (pinfunction "VDD_1") (pintype "power_in"))
    )
    (net (code "4") (name "5V") (class "Default")
      (node (ref "5VREG") (pin "3") (pinfunction "VO_3") (pintype "bidirectional"))
      (node (ref "C6") (pin "+") (pinfunction "1_+") (pintype "passive"))
      (node (ref "JP1") (pin "2") (pinfunction "2_2") (pintype "passive"))
      (node (ref "R4") (pin "2") (pinfunction "2_2") (pintype "passive"))
      (node (ref "R5") (pin "2") (pinfunction "2_2") (pintype "passive"))
      (node (ref "R6") (pin "2") (pinfunction "2_2") (pintype "passive"))
      (node (ref "R7") (pin "2") (pinfunction "2_2") (pintype "passive"))
      (node (ref "SPKR") (pin "1") (pinfunction "1_1") (pintype "passive"))
      (node (ref "U2") (pin "8") (pinfunction "VCC_8") (pintype "power_in"))
      (node (ref "U6") (pin "14") (pinfunction "14_14") (pintype "bidirectional"))
      (node (ref "U7") (pin "14") (pinfunction "14_14") (pintype "bidirectional"))
    )
    (net (code "5") (name "485_D+") (class "Default")
      (node (ref "JP6") (pin "1") (pinfunction "1_1") (pintype "passive"))
      (node (ref "R10") (pin "2") (pinfunction "2_2") (pintype "passive"))
      (node (ref "U2") (pin "6") (pinfunction "A_6") (pintype "bidirectional"))
    )
    (net (code "6") (name "485_D-") (class "Default")
      (node (ref "4P1") (pin "4") (pinfunction "4_4") (pintype "passive"))
      (node (ref "4P2") (pin "4") (pinfunction "4_4") (pintype "passive"))
      (node (ref "R10") (pin "1") (pinfunction "1_1") (pintype "passive"))
      (node (ref "U2") (pin "7") (pinfunction "B_7") (pintype "bidirectional"))
    )
    (net (code "7") (name "BOOT0") (class "Default")
      (node (ref "R2") (pin "2") (pinfunction "2_2") (pintype "passive"))
      (node (ref "U1") (pin "60") (pinfunction "BOOT0_60") (pintype "passive"))
    )
    (net (code "8") (name "BOOT1") (class "Default")
      (node (ref "R1") (pin "2") (pinfunction "2_2") (pintype "passive"))
      (node (ref "U1") (pin "28") (pinfunction "PB1_2_28") (pintype "bidirectional"))
    )
    (net (code "9") (name "CPU_RXD") (class "Default")
      (node (ref "JP7") (pin "2") (pinfunction "2_2") (pintype "passive"))
      (node (ref "U1") (pin "43") (pinfunction "PA10_43") (pintype "bidirectional"))
    )
    (net (code "10") (name "CPU_TXD") (class "Default")
      (node (ref "JP7") (pin "1") (pinfunction "1_1") (pintype "passive"))
      (node (ref "U1") (pin "42") (pinfunction "PA9_42") (pintype "bidirectional"))
    )
    (net (code "11") (name "DATA") (class "Default")
      (node (ref "3P1") (pin "3") (pinfunction "RX/TX_3") (pintype "bidirectional"))
      (node (ref "3P2") (pin "3") (pinfunction "RX/TX_3") (pintype "bidirectional"))
      (node (ref "3P3") (pin "3") (pinfunction "RX/TX_3") (pintype "bidirectional"))
      (node (ref "3P4") (pin "3") (pinfunction "RX/TX_3") (pintype "bidirectional"))
      (node (ref "3P5") (pin "3") (pinfunction "RX/TX_3") (pintype "bidirectional"))
      (node (ref "4P1") (pin "3") (pinfunction "3_3") (pintype "passive"))
      (node (ref "4P2") (pin "3") (pinfunction "3_3") (pintype "passive"))
      (node (ref "JP6") (pin "2") (pinfunction "2_2") (pintype "passive"))
      (node (ref "R23") (pin "2") (pinfunction "2_2") (pintype "passive"))
    )
    (net (code "12") (name "DXLRXD") (class "Default")
      (node (ref "U1") (pin "59") (pinfunction "PB7_59") (pintype "power_in"))
      (node (ref "U9") (pin "1") (pinfunction "CH1A_1") (pintype "bidirectional"))
    )
    (net (code "13") (name "DXLTXD") (class "Default")
      (node (ref "U1") (pin "58") (pinfunction "PB6_58") (pintype "bidirectional"))
      (node (ref "U9") (pin "3") (pinfunction "CH2A_3") (pintype "bidirectional"))
    )
    (net (code "14") (name "DXL_RXD") (class "Default")
      (node (ref "R3") (pin "1") (pinfunction "1_1") (pintype "passive"))
      (node (ref "U9") (pin "5") (pinfunction "CH1B_5") (pintype "bidirectional"))
    )
    (net (code "15") (name "DXL_TXD") (class "Default")
      (node (ref "R9") (pin "1") (pinfunction "1_1") (pintype "passive"))
      (node (ref "U7") (pin "2") (pinfunction "2_2") (pintype "bidirectional"))
      (node (ref "U9") (pin "4") (pinfunction "CH2B_4") (pintype "bidirectional"))
    )
    (net (code "16") (name "ENABLE_DXLPWR") (class "Default")
      (node (ref "R11") (pin "1") (pinfunction "1_1") (pintype "passive"))
      (node (ref "U1") (pin "61") (pinfunction "PB8_61") (pintype "bidirectional"))
    )
    (net (code "17") (name "ENABLE_RX") (class "Default")
      (node (ref "U1") (pin "57") (pinfunction "PB5_57") (pintype "bidirectional"))
      (node (ref "U7") (pin "4") (pinfunction "4_4") (pintype "bidirectional"))
    )
    (net (code "18") (name "ENABLE_TX") (class "Default")
      (node (ref "U1") (pin "40") (pinfunction "PC9_40") (pintype "bidirectional"))
      (node (ref "U2") (pin "2") (pinfunction "~{RE}_2") (pintype "input"))
      (node (ref "U2") (pin "3") (pinfunction "DE_3") (pintype "passive"))
      (node (ref "U7") (pin "1") (pinfunction "1_1") (pintype "bidirectional"))
    )
    (net (code "19") (name "ENABLE_ZIGBEE") (class "Default")
      (node (ref "R14") (pin "1") (pinfunction "1_1") (pintype "passive"))
      (node (ref "U1") (pin "39") (pinfunction "PC8_39") (pintype "bidirectional"))
    )
    (net (code "20") (name "GND") (class "Default")
      (node (ref "3.3V") (pin "C") (pinfunction "C_C") (pintype "passive"))
      (node (ref "3P1") (pin "1") (pinfunction "GND_1") (pintype "bidirectional"))
      (node (ref "3P2") (pin "1") (pinfunction "GND_1") (pintype "bidirectional"))
      (node (ref "3P3") (pin "1") (pinfunction "GND_1") (pintype "bidirectional"))
      (node (ref "3P4") (pin "1") (pinfunction "GND_1") (pintype "bidirectional"))
      (node (ref "3P5") (pin "1") (pinfunction "GND_1") (pintype "bidirectional"))
      (node (ref "3V3REG") (pin "2") (pinfunction "GND_2") (pintype "bidirectional"))
      (node (ref "4P1") (pin "1") (pinfunction "1_1") (pintype "passive"))
      (node (ref "4P2") (pin "1") (pinfunction "1_1") (pintype "passive"))
      (node (ref "5V") (pin "C") (pinfunction "C_C") (pintype "passive"))
      (node (ref "5VREG") (pin "2") (pinfunction "GND_2") (pintype "bidirectional"))
      (node (ref "C1") (pin "2") (pinfunction "2_2") (pintype "passive"))
      (node (ref "C10") (pin "2") (pinfunction "2_2") (pintype "passive"))
      (node (ref "C11") (pin "2") (pinfunction "2_2") (pintype "passive"))
      (node (ref "C12") (pin "2") (pinfunction "2_2") (pintype "passive"))
      (node (ref "C13") (pin "2") (pinfunction "2_2") (pintype "passive"))
      (node (ref "C14") (pin "2") (pinfunction "2_2") (pintype "passive"))
      (node (ref "C15") (pin "2") (pinfunction "2_2") (pintype "passive"))
      (node (ref "C2") (pin "2") (pinfunction "2_2") (pintype "passive"))
      (node (ref "C3") (pin "2") (pinfunction "2_2") (pintype "passive"))
      (node (ref "C4") (pin "2") (pinfunction "2_2") (pintype "passive"))
      (node (ref "C5") (pin "-") (pinfunction "2_-") (pintype "passive"))
      (node (ref "C6") (pin "-") (pinfunction "2_-") (pintype "passive"))
      (node (ref "C7") (pin "2") (pinfunction "2_2") (pintype "passive"))
      (node (ref "C8") (pin "2") (pinfunction "2_2") (pintype "passive"))
      (node (ref "C9") (pin "-") (pinfunction "2_-") (pintype "passive"))
      (node (ref "CPU-POWER") (pin "1") (pinfunction "GND_1") (pintype "bidirectional"))
      (node (ref "DC1") (pin "2") (pinfunction "2_2") (pintype "passive"))
      (node (ref "DC1") (pin "3") (pinfunction "3_3") (pintype "passive"))
      (node (ref "JP1") (pin "1") (pinfunction "1_1") (pintype "passive"))
      (node (ref "JP4") (pin "1") (pinfunction "1_1") (pintype "passive"))
      (node (ref "JP4") (pin "2") (pinfunction "2_2") (pintype "passive"))
      (node (ref "JP4") (pin "3") (pinfunction "3_3") (pintype "passive"))
      (node (ref "JP4") (pin "4") (pinfunction "4_4") (pintype "passive"))
      (node (ref "JP4") (pin "5") (pinfunction "5_5") (pintype "passive"))
      (node (ref "JP4") (pin "6") (pinfunction "6_6") (pintype "passive"))
      (node (ref "JP4") (pin "7") (pinfunction "7_7") (pintype "passive"))
      (node (ref "JP4") (pin "8") (pinfunction "8_8") (pintype "passive"))
      (node (ref "JP7") (pin "3") (pinfunction "3_3") (pintype "passive"))
      (node (ref "JTAG") (pin "3") (pinfunction "3_3") (pintype "passive"))
      (node (ref "JTAG") (pin "5") (pinfunction "5_5") (pintype "passive"))
      (node (ref "JTAG") (pin "9") (pinfunction "9_9") (pintype "passive"))
      (node (ref "Q1") (pin "2") (pinfunction "G$1_2") (pintype "bidirectional"))
      (node (ref "Q1") (pin "4") (pinfunction "G$2_4") (pintype "bidirectional"))
      (node (ref "Q3") (pin "2") (pinfunction "S_2") (pintype "passive"))
      (node (ref "Q5") (pin "3") (pinfunction "C_3") (pintype "passive"))
      (node (ref "R1") (pin "1") (pinfunction "1_1") (pintype "passive"))
      (node (ref "R12") (pin "1") (pinfunction "1_1") (pintype "passive"))
      (node (ref "R16") (pin "1") (pinfunction "1_1") (pintype "passive"))
      (node (ref "R2") (pin "1") (pinfunction "1_1") (pintype "passive"))
      (node (ref "SPKR") (pin "2") (pinfunction "2_2") (pintype "passive"))
      (node (ref "SPKR") (pin "3") (pinfunction "3_3") (pintype "passive"))
      (node (ref "SW1") (pin "2") (pinfunction "S_2") (pintype "passive"))
      (node (ref "SW1") (pin "4") (pinfunction "S1_4") (pintype "passive"))
      (node (ref "SW2") (pin "2") (pinfunction "S_2") (pintype "passive"))
      (node (ref "SW2") (pin "4") (pinfunction "S1_4") (pintype "passive"))
      (node (ref "SW3") (pin "2") (pinfunction "S_2") (pintype "passive"))
      (node (ref "SW3") (pin "4") (pinfunction "S1_4") (pintype "passive"))
      (node (ref "U1") (pin "12") (pinfunction "VSSA_12") (pintype "passive"))
      (node (ref "U1") (pin "18") (pinfunction "VSS_4_18") (pintype "passive"))
      (node (ref "U1") (pin "31") (pinfunction "VSS_1_31") (pintype "passive"))
      (node (ref "U1") (pin "47") (pinfunction "VSS_2_47") (pintype "passive"))
      (node (ref "U1") (pin "63") (pinfunction "VSS_3_63") (pintype "passive"))
      (node (ref "U10") (pin "2") (pinfunction "GND_2") (pintype "bidirectional"))
      (node (ref "U2") (pin "5") (pinfunction "GND_5") (pintype "passive"))
      (node (ref "U3") (pin "10") (pinfunction "RSVDG_10") (pintype "bidirectional"))
      (node (ref "U3") (pin "11") (pinfunction "RSDVG_11") (pintype "bidirectional"))
      (node (ref "U3") (pin "12") (pinfunction "RSVDG_12") (pintype "bidirectional"))
      (node (ref "U3") (pin "13") (pinfunction "GND_13") (pintype "bidirectional"))
      (node (ref "U3") (pin "8") (pinfunction "RSVDG_8") (pintype "bidirectional"))
      (node (ref "U3") (pin "9") (pinfunction "RSVDG_9") (pintype "bidirectional"))
      (node (ref "U4") (pin "10") (pinfunction "GNDR_10") (pintype "bidirectional"))
      (node (ref "U4") (pin "12") (pinfunction "GND_12") (pintype "bidirectional"))
      (node (ref "U4") (pin "13") (pinfunction "GND_13") (pintype "bidirectional"))
      (node (ref "U4") (pin "16") (pinfunction "GND_16") (pintype "bidirectional"))
      (node (ref "U4") (pin "5") (pinfunction "GND_5") (pintype "bidirectional"))
      (node (ref "U5") (pin "17") (pinfunction "GND_17") (pintype "power_in"))
      (node (ref "U5") (pin "20") (pinfunction "GND_20") (pintype "power_in"))
      (node (ref "U5") (pin "24") (pinfunction "AGND_24") (pintype "power_in"))
      (node (ref "U5") (pin "26") (pinfunction "TEST_26") (pintype "input"))
      (node (ref "U5") (pin "4") (pinfunction "GND_4") (pintype "power_in"))
      (node (ref "U6") (pin "7") (pinfunction "7_7") (pintype "bidirectional"))
      (node (ref "U7") (pin "7") (pinfunction "7_7") (pintype "bidirectional"))
      (node (ref "U8") (pin "10") (pinfunction "GND_10") (pintype "power_in"))
      (node (ref "U9") (pin "2") (pinfunction "GND_2") (pintype "bidirectional"))
      (node (ref "USB-DXL") (pin "1") (pinfunction "1_1") (pintype "passive"))
      (node (ref "USB-MICRO") (pin "5") (pinfunction "GND_5") (pintype "bidirectional"))
      (node (ref "USB-MICRO") (pin "E1") (pinfunction "GND_E1") (pintype "bidirectional"))
      (node (ref "USB-MICRO") (pin "E2") (pinfunction "GND_E2") (pintype "bidirectional"))
      (node (ref "USB-MICRO") (pin "P1") (pinfunction "GND_P1") (pintype "bidirectional"))
      (node (ref "USB-MICRO") (pin "P2") (pinfunction "GND_P2") (pintype "bidirectional"))
    )
    (net (code "21") (name "JTCK") (class "Default")
      (node (ref "JTAG") (pin "4") (pinfunction "4_4") (pintype "passive"))
      (node (ref "U1") (pin "49") (pinfunction "PA14_49") (pintype "bidirectional"))
    )
    (net (code "22") (name "JTDI") (class "Default")
      (node (ref "JTAG") (pin "8") (pinfunction "8_8") (pintype "passive"))
      (node (ref "U1") (pin "50") (pinfunction "PA15_50") (pintype "bidirectional"))
    )
    (net (code "23") (name "JTDO") (class "Default")
      (node (ref "JTAG") (pin "6") (pinfunction "6_6") (pintype "passive"))
      (node (ref "U1") (pin "55") (pinfunction "PB3_55") (pintype "bidirectional"))
    )
    (net (code "24") (name "JTMS") (class "Default")
      (node (ref "JTAG") (pin "2") (pinfunction "2_2") (pintype "passive"))
      (node (ref "U1") (pin "46") (pinfunction "PA13_46") (pintype "bidirectional"))
    )
    (net (code "25") (name "LED2") (class "Default")
      (node (ref "R20") (pin "1") (pinfunction "1_1") (pintype "passive"))
      (node (ref "U1") (pin "4") (pinfunction "PC15-OSC32_OUT_4") (pintype "output"))
    )
    (net (code "26") (name "LED3") (class "Default")
      (node (ref "R21") (pin "1") (pinfunction "1_1") (pintype "passive"))
      (node (ref "U1") (pin "33") (pinfunction "PB12_33") (pintype "bidirectional"))
    )
    (net (code "27") (name "LED4") (class "Default")
      (node (ref "R22") (pin "1") (pinfunction "1_1") (pintype "passive"))
      (node (ref "U1") (pin "37") (pinfunction "PC6_37") (pintype "bidirectional"))
    )
    (net (code "28") (name "LED_RX") (class "Default")
      (node (ref "R19") (pin "1") (pinfunction "1_1") (pintype "passive"))
      (node (ref "U1") (pin "3") (pinfunction "PC14-OSC32_IN_3") (pintype "input"))
    )
    (net (code "29") (name "LED_TX") (class "Default")
      (node (ref "R18") (pin "1") (pinfunction "1_1") (pintype "passive"))
      (node (ref "U1") (pin "2") (pinfunction "PC13-TAMPER-RTC_2") (pintype "input"))
    )
    (net (code "30") (name "NJTRST") (class "Default")
      (node (ref "JTAG") (pin "10") (pinfunction "10_10") (pintype "passive"))
      (node (ref "U1") (pin "56") (pinfunction "PB4_56") (pintype "bidirectional"))
    )
    (net (code "31") (name "Net-(3.3V-PadA)") (class "Default")
      (node (ref "3.3V") (pin "A") (pinfunction "A_A") (pintype "passive"))
      (node (ref "R8") (pin "1") (pinfunction "1_1") (pintype "passive"))
    )
    (net (code "32") (name "Net-(5V-PadA)") (class "Default")
      (node (ref "5V") (pin "A") (pinfunction "A_A") (pintype "passive"))
      (node (ref "R7") (pin "1") (pinfunction "1_1") (pintype "passive"))
    )
    (net (code "33") (name "Net-(CPU-POWER-RX{slash}TX)") (class "Default")
      (node (ref "CPU-POWER") (pin "3") (pinfunction "RX/TX_3") (pintype "bidirectional"))
      (node (ref "R23") (pin "1") (pinfunction "1_1") (pintype "passive"))
    )
    (net (code "34") (name "Net-(MODE-PadC)") (class "Default")
      (node (ref "MODE") (pin "C") (pinfunction "C_C") (pintype "passive"))
      (node (ref "R21") (pin "2") (pinfunction "2_2") (pintype "passive"))
    )
    (net (code "35") (name "Net-(Q2-G)") (class "Default")
      (node (ref "Q2") (pin "1") (pinfunction "G_1") (pintype "passive"))
      (node (ref "Q3") (pin "3") (pinfunction "D_3") (pintype "passive"))
      (node (ref "R13") (pin "2") (pinfunction "2_2") (pintype "passive"))
    )
    (net (code "36") (name "Net-(Q3-G)") (class "Default")
      (node (ref "Q3") (pin "1") (pinfunction "G_1") (pintype "passive"))
      (node (ref "R11") (pin "2") (pinfunction "2_2") (pintype "passive"))
      (node (ref "R12") (pin "2") (pinfunction "2_2") (pintype "passive"))
    )
    (net (code "37") (name "Net-(Q4-B)") (class "Default")
      (node (ref "Q4") (pin "1") (pinfunction "B_1") (pintype "passive"))
      (node (ref "R14") (pin "2") (pinfunction "2_2") (pintype "passive"))
    )
    (net (code "38") (name "Net-(Q5-B)") (class "Default")
      (node (ref "Q5") (pin "1") (pinfunction "B_1") (pintype "passive"))
      (node (ref "R15") (pin "2") (pinfunction "2_2") (pintype "passive"))
    )
    (net (code "39") (name "Net-(Q5-E)") (class "Default")
      (node (ref "Q5") (pin "2") (pinfunction "E_2") (pintype "passive"))
      (node (ref "SPKR") (pin "4") (pinfunction "4_4") (pintype "passive"))
    )
    (net (code "40") (name "Net-(R3-Pad2)") (class "Default")
      (node (ref "R3") (pin "2") (pinfunction "2_2") (pintype "passive"))
      (node (ref "U6") (pin "3") (pinfunction "3_3") (pintype "bidirectional"))
    )
    (net (code "41") (name "Net-(R18-Pad2)") (class "Default")
      (node (ref "R18") (pin "2") (pinfunction "2_2") (pintype "passive"))
      (node (ref "TX") (pin "C") (pinfunction "C_C") (pintype "passive"))
    )
    (net (code "42") (name "Net-(R19-Pad2)") (class "Default")
      (node (ref "R19") (pin "2") (pinfunction "2_2") (pintype "passive"))
      (node (ref "RX") (pin "C") (pinfunction "C_C") (pintype "passive"))
    )
    (net (code "43") (name "Net-(R20-Pad2)") (class "Default")
      (node (ref "R20") (pin "2") (pinfunction "2_2") (pintype "passive"))
      (node (ref "RESET") (pin "C") (pinfunction "C_C") (pintype "passive"))
    )
    (net (code "44") (name "Net-(R22-Pad2)") (class "Default")
      (node (ref "R22") (pin "2") (pinfunction "2_2") (pintype "passive"))
      (node (ref "START") (pin "C") (pinfunction "C_C") (pintype "passive"))
    )
    (net (code "45") (name "Net-(R24-Pad2)") (class "Default")
      (node (ref "R24") (pin "2") (pinfunction "2_2") (pintype "passive"))
      (node (ref "USBTX") (pin "C") (pinfunction "C_C") (pintype "passive"))
    )
    (net (code "46") (name "Net-(R25-Pad2)") (class "Default")
      (node (ref "R25") (pin "2") (pinfunction "2_2") (pintype "passive"))
      (node (ref "USBRX") (pin "C") (pinfunction "C_C") (pintype "passive"))
    )
    (net (code "47") (name "Net-(U2-DI)") (class "Default")
      (node (ref "R9") (pin "2") (pinfunction "2_2") (pintype "passive"))
      (node (ref "U2") (pin "4") (pinfunction "DI_4") (pintype "input"))
    )
    (net (code "48") (name "Net-(U2-RO)") (class "Default")
      (node (ref "R6") (pin "1") (pinfunction "1_1") (pintype "passive"))
      (node (ref "U2") (pin "1") (pinfunction "RO_1") (pintype "output"))
      (node (ref "U6") (pin "1") (pinfunction "1_1") (pintype "bidirectional"))
    )
    (net (code "49") (name "Net-(U3-PLL)") (class "Default")
      (node (ref "C12") (pin "1") (pinfunction "1_1") (pintype "passive"))
      (node (ref "U3") (pin "14") (pinfunction "PLL_14") (pintype "bidirectional"))
    )
    (net (code "50") (name "Net-(U5-RESET)") (class "Default")
      (node (ref "FTDI-RESET") (pin "2") (pinfunction "2_2") (pintype "passive"))
      (node (ref "U5") (pin "18") (pinfunction "RESET_18") (pintype "input"))
    )
    (net (code "51") (name "Net-(U5-RXLED)") (class "Default")
      (node (ref "R25") (pin "1") (pinfunction "1_1") (pintype "passive"))
      (node (ref "U5") (pin "21") (pinfunction "RXLED_21") (pintype "input"))
    )
    (net (code "52") (name "Net-(U5-TXLED)") (class "Default")
      (node (ref "R24") (pin "1") (pinfunction "1_1") (pintype "passive"))
      (node (ref "U5") (pin "22") (pinfunction "TXLED_22") (pintype "input"))
    )
    (net (code "53") (name "Net-(U10-CH1A)") (class "Default")
      (node (ref "U10") (pin "1") (pinfunction "CH1A_1") (pintype "bidirectional"))
      (node (ref "U7") (pin "3") (pinfunction "3_3") (pintype "bidirectional"))
      (node (ref "U7") (pin "5") (pinfunction "5_5") (pintype "bidirectional"))
    )
    (net (code "54") (name "PC_RXD") (class "Default")
      (node (ref "U1") (pin "30") (pinfunction "PB11_30") (pintype "bidirectional"))
      (node (ref "U5") (pin "30") (pinfunction "TXD_30") (pintype "output"))
    )
    (net (code "55") (name "PC_TXD") (class "Default")
      (node (ref "U1") (pin "29") (pinfunction "PB10_29") (pintype "bidirectional"))
      (node (ref "U5") (pin "2") (pinfunction "RXD_2") (pintype "input"))
    )
    (net (code "56") (name "PIN_PA8") (class "Default")
      (node (ref "JP2") (pin "8") (pinfunction "8_8") (pintype "passive"))
      (node (ref "U1") (pin "41") (pinfunction "PA8_41") (pintype "bidirectional"))
    )
    (net (code "57") (name "PIN_PC7") (class "Default")
      (node (ref "U1") (pin "38") (pinfunction "PC7_38") (pintype "bidirectional"))
    )
    (net (code "58") (name "RESET") (class "Default")
      (node (ref "SW1") (pin "1") (pinfunction "P_1") (pintype "passive"))
      (node (ref "SW1") (pin "3") (pinfunction "P1_3") (pintype "passive"))
      (node (ref "U1") (pin "7") (pinfunction "NRST_7") (pintype "output"))
    )
    (net (code "59") (name "RXD_TTL") (class "Default")
      (node (ref "R4") (pin "1") (pinfunction "1_1") (pintype "passive"))
      (node (ref "U6") (pin "2") (pinfunction "2_2") (pintype "bidirectional"))
      (node (ref "U7") (pin "6") (pinfunction "6_6") (pintype "bidirectional"))
    )
    (net (code "60") (name "SIG_ACC_CS") (class "Default")
      (node (ref "U1") (pin "51") (pinfunction "PC10_51") (pintype "bidirectional"))
      (node (ref "U4") (pin "8") (pinfunction "CS_8") (pintype "bidirectional"))
    )
    (net (code "61") (name "SIG_ADC0") (class "Default")
      (node (ref "R16") (pin "2") (pinfunction "2_2") (pintype "passive"))
      (node (ref "R17") (pin "1") (pinfunction "1_1") (pintype "passive"))
      (node (ref "U1") (pin "8") (pinfunction "PC0_8") (pintype "bidirectional"))
    )
    (net (code "62") (name "SIG_ADC1") (class "Default")
      (node (ref "JP5") (pin "1") (pinfunction "1_1") (pintype "passive"))
      (node (ref "U1") (pin "9") (pinfunction "PC1_9") (pintype "bidirectional"))
    )
    (net (code "63") (name "SIG_ADC2") (class "Default")
      (node (ref "JP5") (pin "2") (pinfunction "2_2") (pintype "passive"))
      (node (ref "U1") (pin "10") (pinfunction "PC2_10") (pintype "bidirectional"))
    )
    (net (code "64") (name "SIG_ADC3") (class "Default")
      (node (ref "JP5") (pin "3") (pinfunction "3_3") (pintype "passive"))
      (node (ref "U1") (pin "11") (pinfunction "PC3_11") (pintype "bidirectional"))
    )
    (net (code "65") (name "SIG_ADC4") (class "Default")
      (node (ref "JP5") (pin "4") (pinfunction "4_4") (pintype "passive"))
      (node (ref "U1") (pin "14") (pinfunction "PA0-WKUP_14") (pintype "bidirectional"))
    )
    (net (code "66") (name "SIG_ADC5") (class "Default")
      (node (ref "JP5") (pin "5") (pinfunction "5_5") (pintype "passive"))
      (node (ref "U1") (pin "15") (pinfunction "PA1_15") (pintype "bidirectional"))
    )
    (net (code "67") (name "SIG_ADC6") (class "Default")
      (node (ref "JP5") (pin "6") (pinfunction "6_6") (pintype "passive"))
      (node (ref "U1") (pin "16") (pinfunction "PA2_16") (pintype "bidirectional"))
    )
    (net (code "68") (name "SIG_ADC7") (class "Default")
      (node (ref "JP5") (pin "7") (pinfunction "7_7") (pintype "passive"))
      (node (ref "U1") (pin "17") (pinfunction "PA3_17") (pintype "bidirectional"))
    )
    (net (code "69") (name "SIG_ADC8") (class "Default")
      (node (ref "JP5") (pin "8") (pinfunction "8_8") (pintype "passive"))
      (node (ref "U1") (pin "20") (pinfunction "PA4_20") (pintype "bidirectional"))
    )
    (net (code "70") (name "SIG_ADC9") (class "Default")
      (node (ref "JP2") (pin "1") (pinfunction "1_1") (pintype "passive"))
      (node (ref "U1") (pin "21") (pinfunction "PA5_21") (pintype "bidirectional"))
    )
    (net (code "71") (name "SIG_ADC10") (class "Default")
      (node (ref "JP2") (pin "2") (pinfunction "2_2") (pintype "passive"))
      (node (ref "U1") (pin "22") (pinfunction "PA6_22") (pintype "bidirectional"))
    )
    (net (code "72") (name "SIG_ADC11") (class "Default")
      (node (ref "JP2") (pin "3") (pinfunction "3_3") (pintype "passive"))
      (node (ref "U1") (pin "23") (pinfunction "PA7_23") (pintype "power_in"))
    )
    (net (code "73") (name "SIG_ADC12") (class "Default")
      (node (ref "JP2") (pin "4") (pinfunction "4_4") (pintype "passive"))
      (node (ref "U1") (pin "24") (pinfunction "PC4_24") (pintype "passive"))
    )
    (net (code "74") (name "SIG_ADC13") (class "Default")
      (node (ref "JP2") (pin "5") (pinfunction "5_5") (pintype "passive"))
      (node (ref "U1") (pin "25") (pinfunction "PC5_25") (pintype "bidirectional"))
    )
    (net (code "75") (name "SIG_ADC14") (class "Default")
      (node (ref "JP2") (pin "6") (pinfunction "6_6") (pintype "passive"))
      (node (ref "U1") (pin "26") (pinfunction "PB0_26") (pintype "bidirectional"))
    )
    (net (code "76") (name "SIG_ADC15") (class "Default")
      (node (ref "JP2") (pin "7") (pinfunction "7_7") (pintype "passive"))
      (node (ref "U1") (pin "27") (pinfunction "PB1_27") (pintype "bidirectional"))
    )
    (net (code "77") (name "SIG_BUZZER") (class "Default")
      (node (ref "R15") (pin "1") (pinfunction "1_1") (pintype "passive"))
      (node (ref "U1") (pin "62") (pinfunction "PB9_62") (pintype "bidirectional"))
    )
    (net (code "78") (name "SIG_GYRO_CS") (class "Default")
      (node (ref "U1") (pin "52") (pinfunction "PC11_52") (pintype "bidirectional"))
      (node (ref "U3") (pin "5") (pinfunction "CS_5") (pintype "bidirectional"))
    )
    (net (code "79") (name "SIG_MISO") (class "Default")
      (node (ref "U1") (pin "35") (pinfunction "PB14_35") (pintype "bidirectional"))
      (node (ref "U3") (pin "4") (pinfunction "SDO_4") (pintype "bidirectional"))
      (node (ref "U4") (pin "7") (pinfunction "SA0/SDO_7") (pintype "bidirectional"))
    )
    (net (code "80") (name "SIG_MOSI") (class "Default")
      (node (ref "U1") (pin "36") (pinfunction "PB15_36") (pintype "bidirectional"))
      (node (ref "U3") (pin "3") (pinfunction "SDA/SDI_3") (pintype "bidirectional"))
      (node (ref "U4") (pin "6") (pinfunction "SDA/SDI_6") (pintype "bidirectional"))
    )
    (net (code "81") (name "SIG_SCK") (class "Default")
      (node (ref "U1") (pin "34") (pinfunction "PB13_34") (pintype "bidirectional"))
      (node (ref "U3") (pin "2") (pinfunction "SCL_2") (pintype "bidirectional"))
      (node (ref "U4") (pin "4") (pinfunction "SCL/SPC_4") (pintype "bidirectional"))
    )
    (net (code "82") (name "SW_MODE") (class "Default")
      (node (ref "SW3") (pin "1") (pinfunction "P_1") (pintype "passive"))
      (node (ref "SW3") (pin "3") (pinfunction "P1_3") (pintype "passive"))
      (node (ref "U1") (pin "44") (pinfunction "PA11_44") (pintype "bidirectional"))
    )
    (net (code "83") (name "SW_START") (class "Default")
      (node (ref "SW2") (pin "1") (pinfunction "P_1") (pintype "passive"))
      (node (ref "SW2") (pin "3") (pinfunction "P1_3") (pintype "passive"))
      (node (ref "U1") (pin "45") (pinfunction "PA12_45") (pintype "bidirectional"))
    )
    (net (code "84") (name "TTL_DATA") (class "Default")
      (node (ref "JP6") (pin "3") (pinfunction "3_3") (pintype "passive"))
      (node (ref "R5") (pin "1") (pinfunction "1_1") (pintype "passive"))
      (node (ref "U10") (pin "5") (pinfunction "CH1B_5") (pintype "bidirectional"))
    )
    (net (code "85") (name "USBDM") (class "Default")
      (node (ref "U5") (pin "15") (pinfunction "USBDM_15") (pintype "bidirectional"))
      (node (ref "USB-DXL") (pin "3") (pinfunction "3_3") (pintype "passive"))
      (node (ref "USB-MICRO") (pin "2") (pinfunction "DM_2") (pintype "bidirectional"))
    )
    (net (code "86") (name "USBDP") (class "Default")
      (node (ref "U5") (pin "14") (pinfunction "USBDP_14") (pintype "bidirectional"))
      (node (ref "USB-DXL") (pin "2") (pinfunction "2_2") (pintype "passive"))
      (node (ref "USB-MICRO") (pin "3") (pinfunction "DP_3") (pintype "bidirectional"))
    )
    (net (code "87") (name "VBUS") (class "Default")
      (node (ref "FTDI-RESET") (pin "1") (pinfunction "1_1") (pintype "passive"))
      (node (ref "U5") (pin "19") (pinfunction "VCC_19") (pintype "power_in"))
      (node (ref "USB-DXL") (pin "4") (pinfunction "4_4") (pintype "passive"))
      (node (ref "USB-MICRO") (pin "1") (pinfunction "VCC_1") (pintype "bidirectional"))
    )
    (net (code "88") (name "VDD_DXL") (class "Default")
      (node (ref "3P1") (pin "2") (pinfunction "VCC_2") (pintype "bidirectional"))
      (node (ref "3P2") (pin "2") (pinfunction "VCC_2") (pintype "bidirectional"))
      (node (ref "3P3") (pin "2") (pinfunction "VCC_2") (pintype "bidirectional"))
      (node (ref "3P4") (pin "2") (pinfunction "VCC_2") (pintype "bidirectional"))
      (node (ref "3P5") (pin "2") (pinfunction "VCC_2") (pintype "bidirectional"))
      (node (ref "4P1") (pin "2") (pinfunction "2_2") (pintype "passive"))
      (node (ref "4P2") (pin "2") (pinfunction "2_2") (pintype "passive"))
      (node (ref "Q2") (pin "3") (pinfunction "D_3") (pintype "passive"))
    )
    (net (code "89") (name "VIN") (class "Default")
      (node (ref "3V3REG") (pin "1") (pinfunction "VI_1") (pintype "bidirectional"))
      (node (ref "5VREG") (pin "1") (pinfunction "VI_1") (pintype "bidirectional"))
      (node (ref "C5") (pin "+") (pinfunction "1_+") (pintype "passive"))
      (node (ref "CPU-POWER") (pin "2") (pinfunction "VCC_2") (pintype "bidirectional"))
      (node (ref "DC1") (pin "1") (pinfunction "1_1") (pintype "passive"))
      (node (ref "JP1") (pin "4") (pinfunction "4_4") (pintype "passive"))
      (node (ref "Q2") (pin "2") (pinfunction "S_2") (pintype "passive"))
      (node (ref "R13") (pin "1") (pinfunction "1_1") (pintype "passive"))
      (node (ref "R17") (pin "2") (pinfunction "2_2") (pintype "passive"))
    )
    (net (code "90") (name "XTAL1") (class "Default")
      (node (ref "C3") (pin "1") (pinfunction "1_1") (pintype "passive"))
      (node (ref "Q1") (pin "3") (pinfunction "P$2_3") (pintype "bidirectional"))
      (node (ref "U1") (pin "5") (pinfunction "PD0_OSC_IN_5") (pintype "input"))
    )
    (net (code "91") (name "XTAL2") (class "Default")
      (node (ref "C2") (pin "1") (pinfunction "1_1") (pintype "passive"))
      (node (ref "Q1") (pin "1") (pinfunction "P$1_1") (pintype "bidirectional"))
      (node (ref "U1") (pin "6") (pinfunction "PD1_OSC_OUT_6") (pintype "output"))
    )
    (net (code "92") (name "ZIGBEE_RXD") (class "Default")
      (node (ref "U1") (pin "54") (pinfunction "PD2_54") (pintype "bidirectional"))
      (node (ref "U8") (pin "2") (pinfunction "DOUT_2") (pintype "output"))
    )
    (net (code "93") (name "ZIGBEE_TXD") (class "Default")
      (node (ref "U1") (pin "53") (pinfunction "PC12_53") (pintype "bidirectional"))
      (node (ref "U8") (pin "3") (pinfunction "DIN_3") (pintype "input"))
    )
    (net (code "94") (name "unconnected-(H1-MOUNT-PadB3,2)") (class "Default")
      (node (ref "H1") (pin "B3,2") (pinfunction "MOUNT_B3,2") (pintype "passive"))
    )
    (net (code "95") (name "unconnected-(H2-MOUNT-PadB3,2)") (class "Default")
      (node (ref "H2") (pin "B3,2") (pinfunction "MOUNT_B3,2") (pintype "passive"))
    )
    (net (code "96") (name "unconnected-(H3-MOUNT-PadB3,2)") (class "Default")
      (node (ref "H3") (pin "B3,2") (pinfunction "MOUNT_B3,2") (pintype "passive"))
    )
    (net (code "97") (name "unconnected-(H4-MOUNT-PadB3,2)") (class "Default")
      (node (ref "H4") (pin "B3,2") (pinfunction "MOUNT_B3,2") (pintype "passive"))
    )
    (net (code "98") (name "unconnected-(JTAG-Pad7)") (class "Default")
      (node (ref "JTAG") (pin "7") (pinfunction "7_7") (pintype "passive"))
    )
    (net (code "99") (name "unconnected-(U3-INT1-Pad7)") (class "Default")
      (node (ref "U3") (pin "7") (pinfunction "INT1_7") (pintype "bidirectional"))
    )
    (net (code "100") (name "unconnected-(U3-INT2-Pad6)") (class "Default")
      (node (ref "U3") (pin "6") (pinfunction "INT2_6") (pintype "bidirectional"))
    )
    (net (code "101") (name "unconnected-(U4-INT1-Pad11)") (class "Default")
      (node (ref "U4") (pin "11") (pinfunction "INT1_11") (pintype "bidirectional"))
    )
    (net (code "102") (name "unconnected-(U4-INT2-Pad9)") (class "Default")
      (node (ref "U4") (pin "9") (pinfunction "INT2_9") (pintype "bidirectional"))
    )
    (net (code "103") (name "unconnected-(U5-CTS-Pad8)") (class "Default")
      (node (ref "U5") (pin "8") (pinfunction "CTS_8") (pintype "input"))
    )
    (net (code "104") (name "unconnected-(U5-DCD-Pad7)") (class "Default")
      (node (ref "U5") (pin "7") (pinfunction "DCD_7") (pintype "input"))
    )
    (net (code "105") (name "unconnected-(U5-DSR-Pad6)") (class "Default")
      (node (ref "U5") (pin "6") (pinfunction "DSR_6") (pintype "input"))
    )
    (net (code "106") (name "unconnected-(U5-DTR-Pad31)") (class "Default")
      (node (ref "U5") (pin "31") (pinfunction "DTR_31") (pintype "output"))
    )
    (net (code "107") (name "unconnected-(U5-OSCI-Pad27)") (class "Default")
      (node (ref "U5") (pin "27") (pinfunction "OSCI_27") (pintype "input"))
    )
    (net (code "108") (name "unconnected-(U5-OSCO-Pad28)") (class "Default")
      (node (ref "U5") (pin "28") (pinfunction "OSCO_28") (pintype "output"))
    )
    (net (code "109") (name "unconnected-(U5-PWREN-Pad11)") (class "Default")
      (node (ref "U5") (pin "11") (pinfunction "PWREN_11") (pintype "input"))
    )
    (net (code "110") (name "unconnected-(U5-RI-Pad3)") (class "Default")
      (node (ref "U5") (pin "3") (pinfunction "RI_3") (pintype "input"))
    )
    (net (code "111") (name "unconnected-(U5-RTS-Pad32)") (class "Default")
      (node (ref "U5") (pin "32") (pinfunction "RTS_32") (pintype "output"))
    )
    (net (code "112") (name "unconnected-(U5-SLEEP-Pad9)") (class "Default")
      (node (ref "U5") (pin "9") (pinfunction "SLEEP_9") (pintype "input"))
    )
    (net (code "113") (name "unconnected-(U5-TXDEN-Pad10)") (class "Default")
      (node (ref "U5") (pin "10") (pinfunction "TXDEN_10") (pintype "input"))
    )
    (net (code "114") (name "unconnected-(U8-CTS-Pad12)") (class "Default")
      (node (ref "U8") (pin "12") (pinfunction "CTS_12") (pintype "output"))
    )
    (net (code "115") (name "unconnected-(U8-DIO0-Pad20)") (class "Default")
      (node (ref "U8") (pin "20") (pinfunction "DIO0_20") (pintype "bidirectional"))
    )
    (net (code "116") (name "unconnected-(U8-DIO1-Pad19)") (class "Default")
      (node (ref "U8") (pin "19") (pinfunction "DIO1_19") (pintype "bidirectional"))
    )
    (net (code "117") (name "unconnected-(U8-DIO2-Pad18)") (class "Default")
      (node (ref "U8") (pin "18") (pinfunction "DIO2_18") (pintype "bidirectional"))
    )
    (net (code "118") (name "unconnected-(U8-DIO3-Pad17)") (class "Default")
      (node (ref "U8") (pin "17") (pinfunction "DIO3_17") (pintype "bidirectional"))
    )
    (net (code "119") (name "unconnected-(U8-DIO4-Pad11)") (class "Default")
      (node (ref "U8") (pin "11") (pinfunction "DIO4_11") (pintype "bidirectional"))
    )
    (net (code "120") (name "unconnected-(U8-DIO5-Pad15)") (class "Default")
      (node (ref "U8") (pin "15") (pinfunction "DIO5_15") (pintype "bidirectional"))
    )
    (net (code "121") (name "unconnected-(U8-DIO9-Pad13)") (class "Default")
      (node (ref "U8") (pin "13") (pinfunction "DIO9_13") (pintype "bidirectional"))
    )
    (net (code "122") (name "unconnected-(U8-DIO11-Pad7)") (class "Default")
      (node (ref "U8") (pin "7") (pinfunction "DIO11_7") (pintype "bidirectional"))
    )
    (net (code "123") (name "unconnected-(U8-DIO12-Pad4)") (class "Default")
      (node (ref "U8") (pin "4") (pinfunction "DIO12_4") (pintype "bidirectional"))
    )
    (net (code "124") (name "unconnected-(U8-DTR-Pad9)") (class "Default")
      (node (ref "U8") (pin "9") (pinfunction "DTR_9") (pintype "bidirectional"))
    )
    (net (code "125") (name "unconnected-(U8-RES-Pad8)") (class "Default")
      (node (ref "U8") (pin "8") (pinfunction "RES_8") (pintype "bidirectional"))
    )
    (net (code "126") (name "unconnected-(U8-RES-Pad14)") (class "Default")
      (node (ref "U8") (pin "14") (pinfunction "RES_14") (pintype "bidirectional"))
    )
    (net (code "127") (name "unconnected-(U8-RESET-Pad5)") (class "Default")
      (node (ref "U8") (pin "5") (pinfunction "RESET_5") (pintype "input"))
    )
    (net (code "128") (name "unconnected-(U8-RSSI-Pad6)") (class "Default")
      (node (ref "U8") (pin "6") (pinfunction "RSSI_6") (pintype "bidirectional"))
    )
    (net (code "129") (name "unconnected-(U8-RTS-Pad16)") (class "Default")
      (node (ref "U8") (pin "16") (pinfunction "RTS_16") (pintype "input"))
    )
    (net (code "130") (name "unconnected-(U10-CH2A-Pad3)") (class "Default")
      (node (ref "U10") (pin "3") (pinfunction "CH2A_3") (pintype "bidirectional"))
    )
    (net (code "131") (name "unconnected-(U10-CH2B-Pad4)") (class "Default")
      (node (ref "U10") (pin "4") (pinfunction "CH2B_4") (pintype "bidirectional"))
    )
    (net (code "132") (name "unconnected-(USB-MICRO-ID-Pad4)") (class "Default")
      (node (ref "USB-MICRO") (pin "4") (pinfunction "ID_4") (pintype "bidirectional"))
    )
  )
)
